# Theremizer.net
KiCad netlist of a schematic drawn in EAGLE
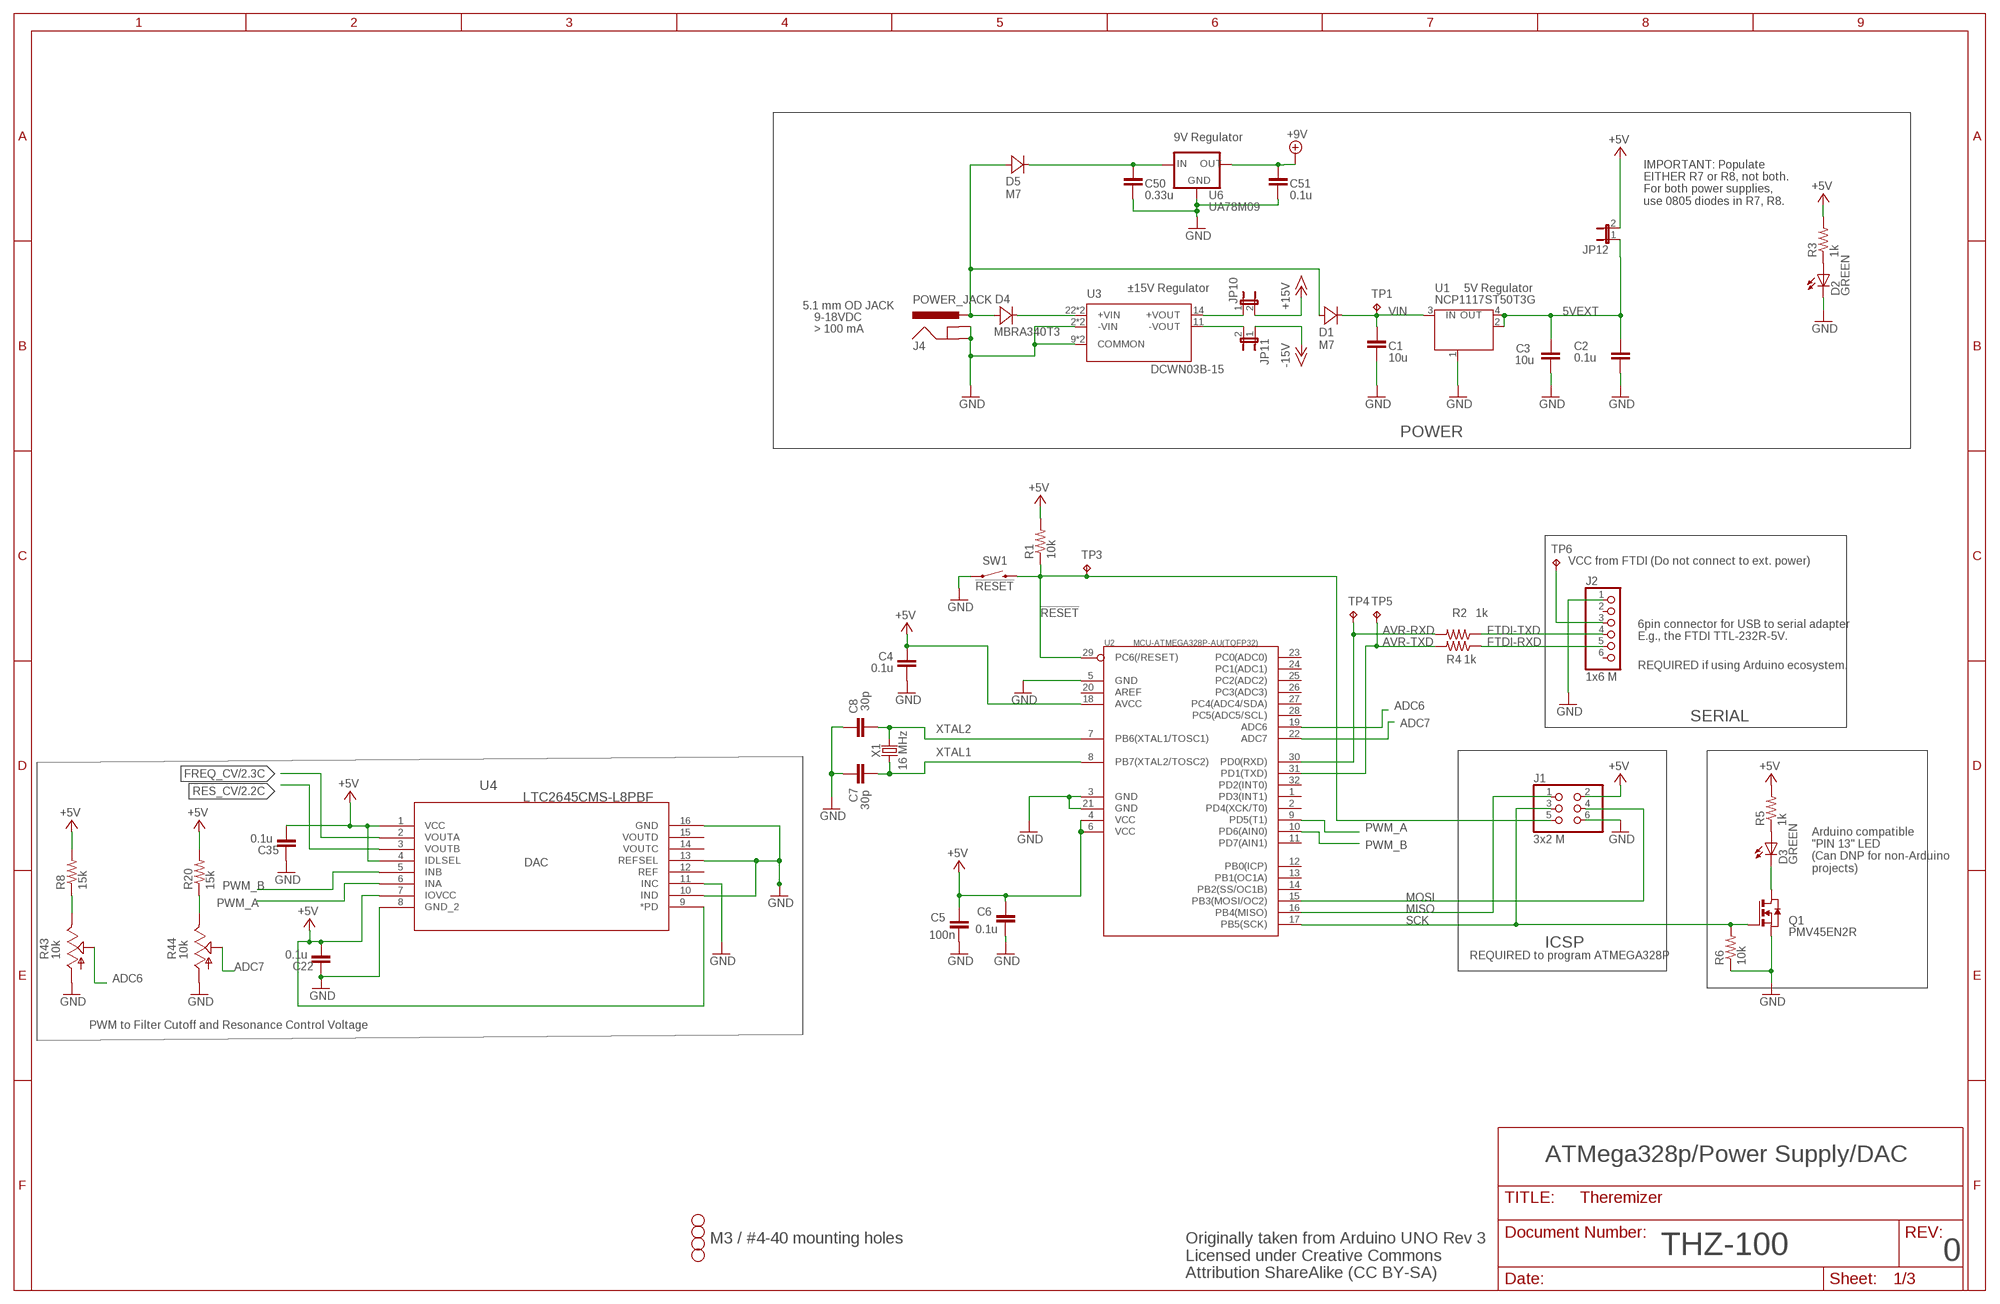
[diagram p0: schematic, sheet 1]
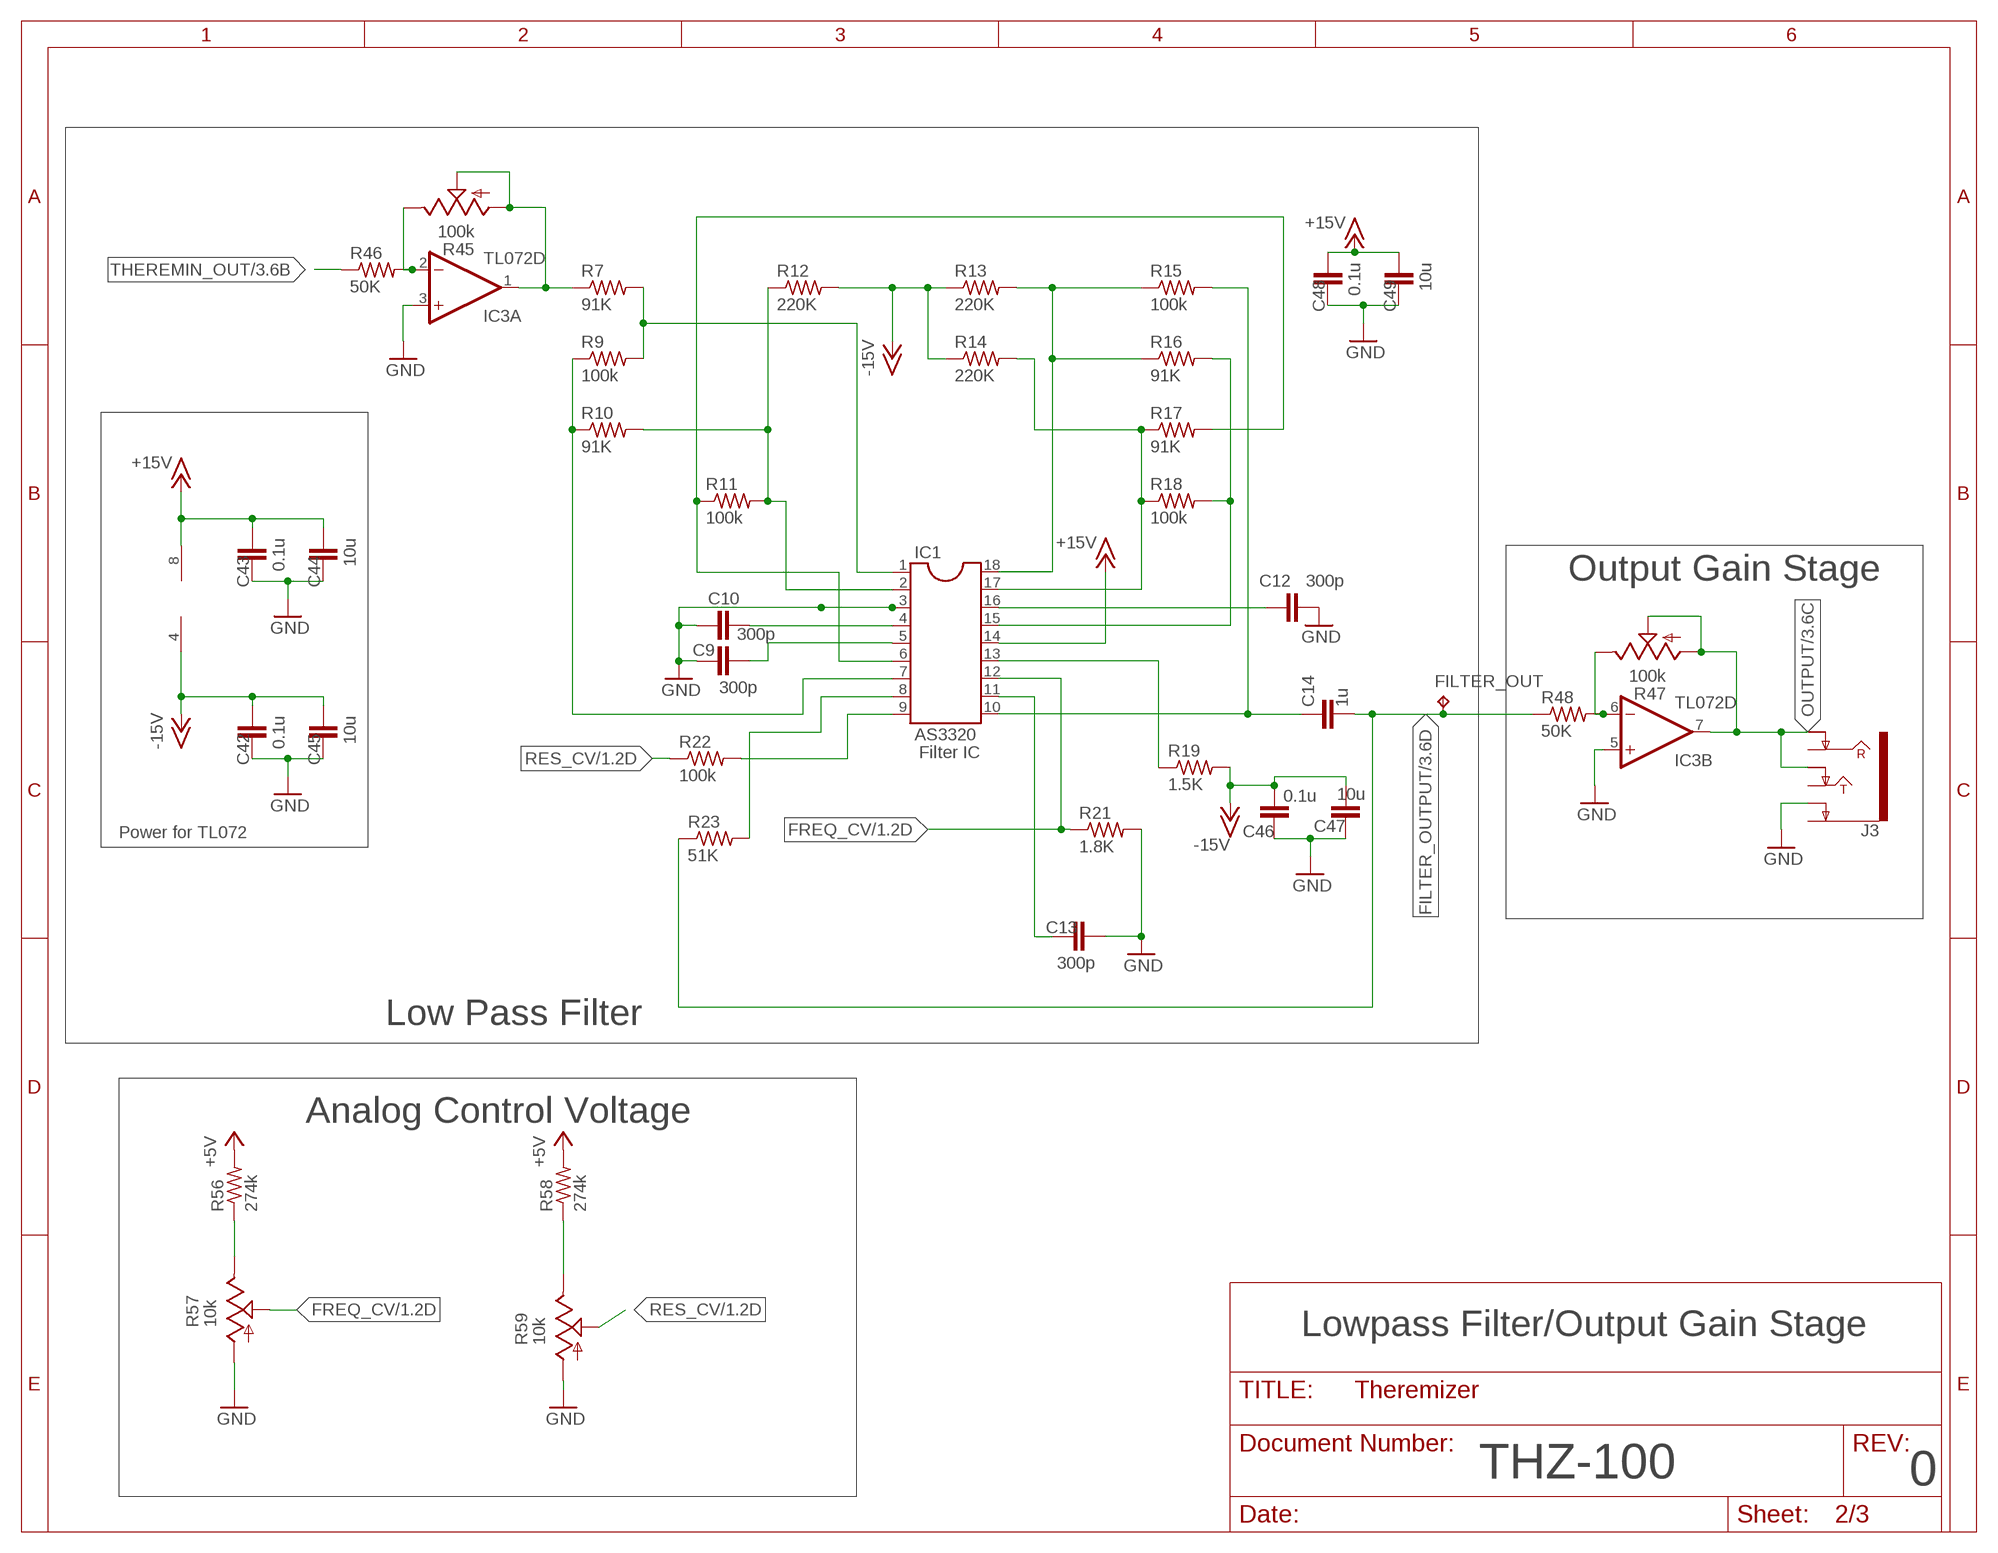
[diagram p1: schematic, sheet 2]
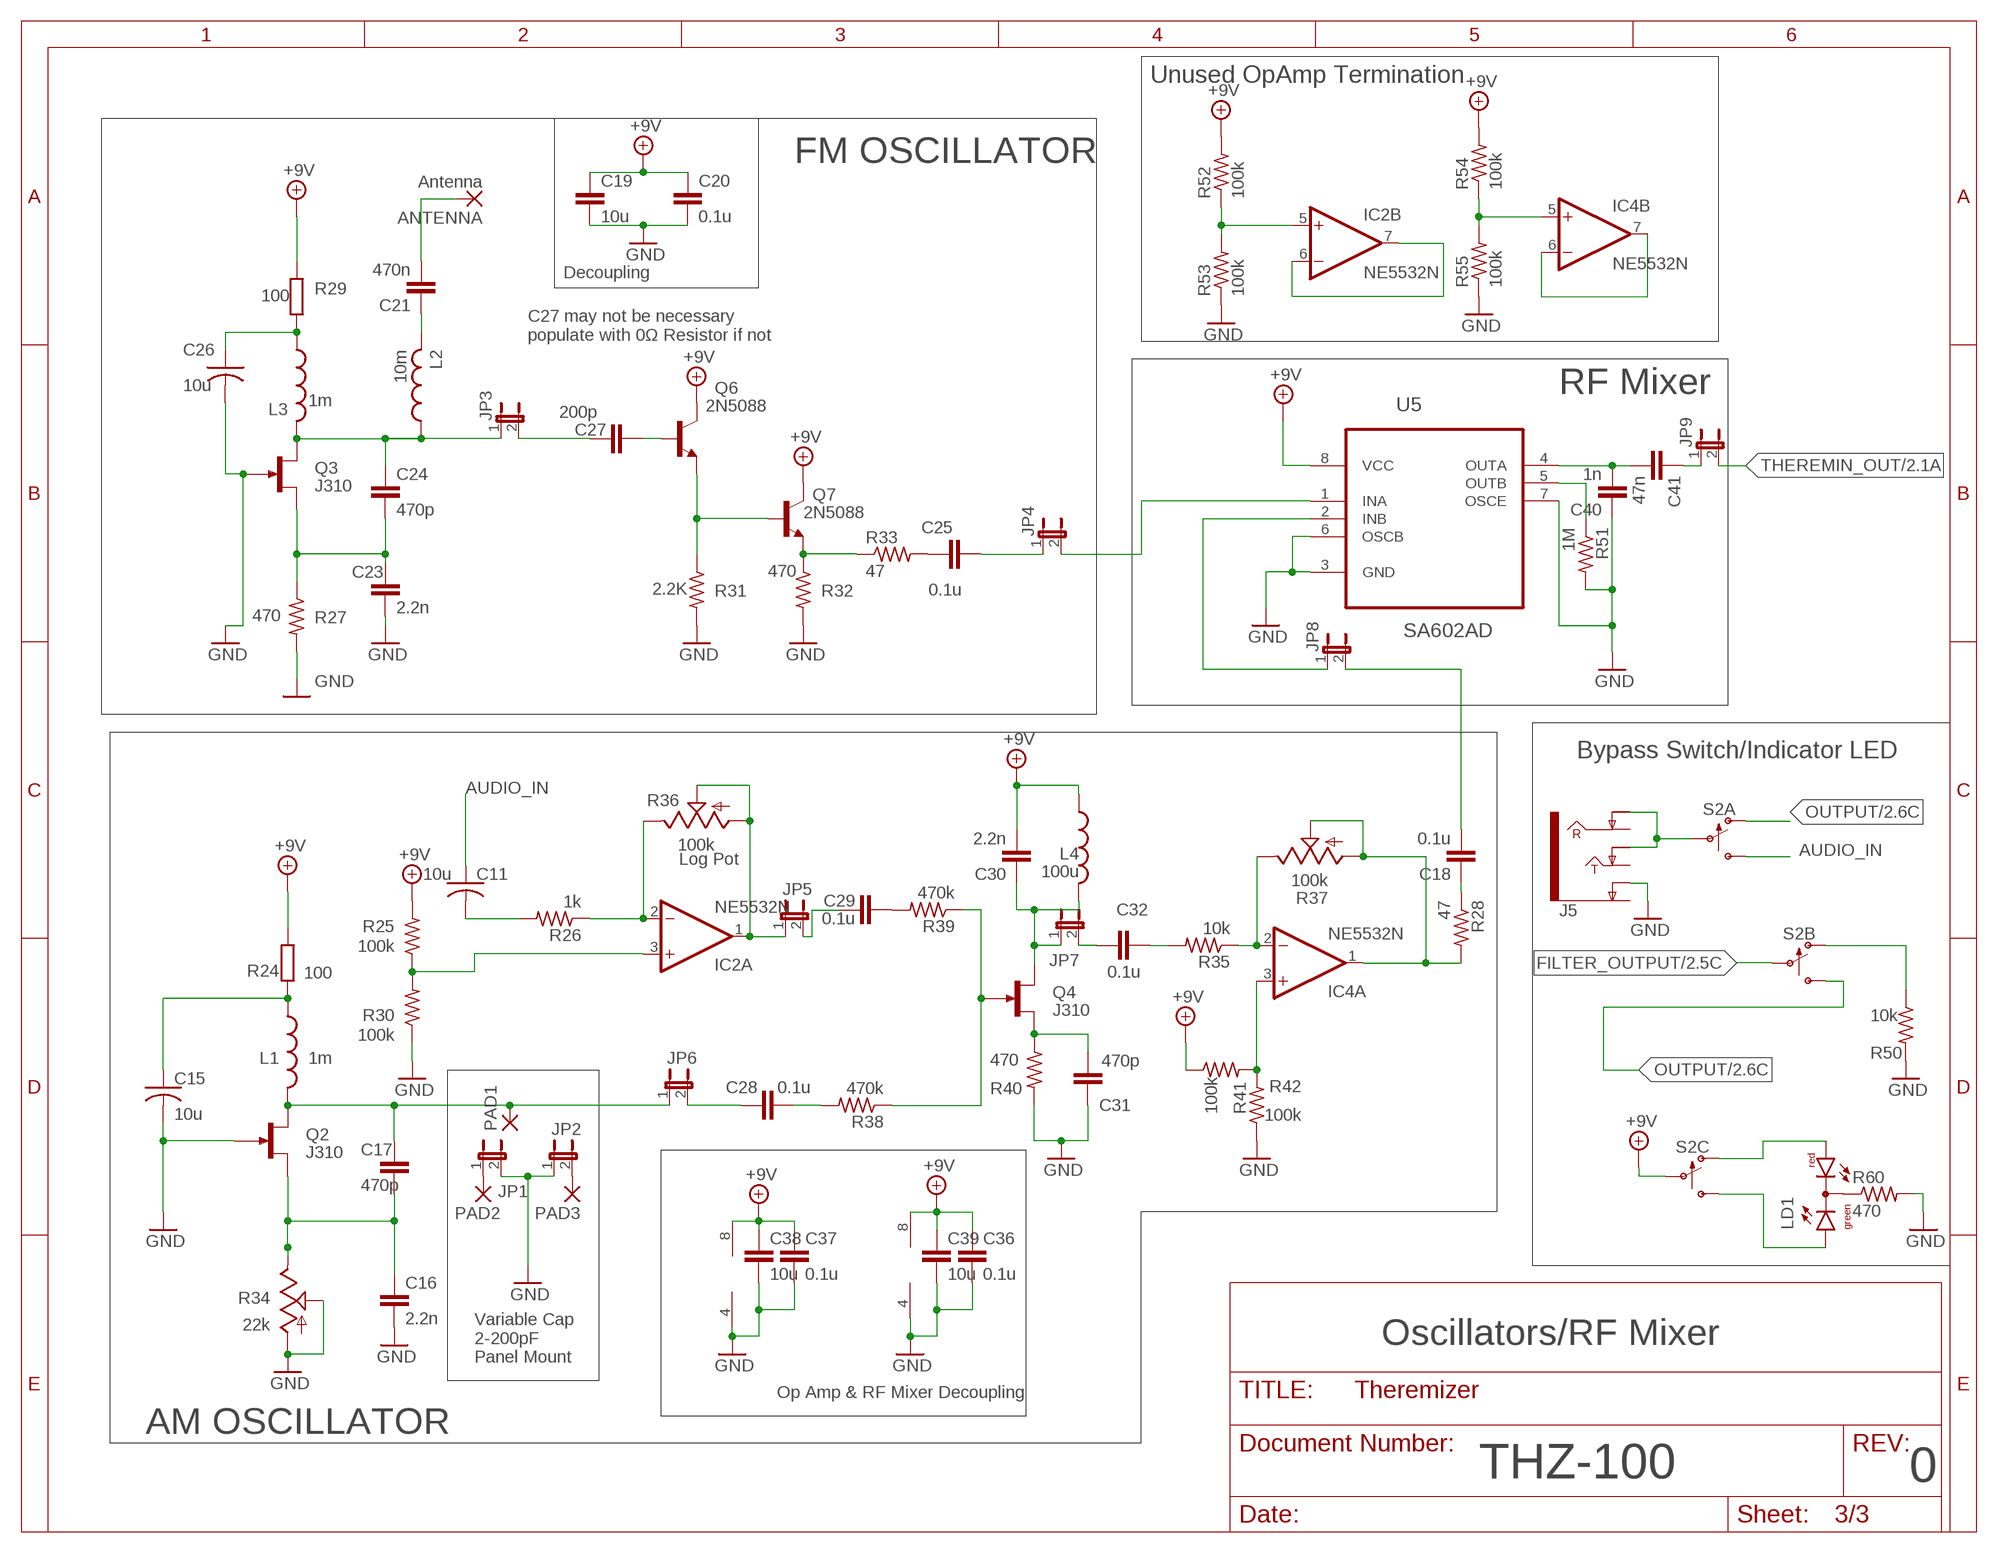
[diagram p2: schematic, sheet 3]

(export (version "E")
  (design (tool "Eeschema 10.0.6"))
  (components
    (comp (ref "ANTENNA")
      (value "Antenna")
      (footprint "eagle-import:2,54_1,1")
      (libsource (lib "eagle-import") (part "2,54/1,1"))
    )
    (comp (ref "C11")
      (value "10u")
      (footprint "eagle-import:C050-025X075")
      (libsource (lib "eagle-import") (part "C-US050-025X075"))
    )
    (comp (ref "C15")
      (value "10u")
      (footprint "eagle-import:C050-025X075")
      (libsource (lib "eagle-import") (part "C-US050-025X075"))
    )
    (comp (ref "C16")
      (value "2.2n")
      (footprint "eagle-import:C0805")
      (libsource (lib "eagle-import") (part "C-EUC0805"))
    )
    (comp (ref "C17")
      (value "470p")
      (footprint "eagle-import:C0805")
      (libsource (lib "eagle-import") (part "C-EUC0805"))
    )
    (comp (ref "C18")
      (value "0.1u")
      (footprint "eagle-import:C0805")
      (libsource (lib "eagle-import") (part "C-EUC0805"))
    )
    (comp (ref "C19")
      (value "10u")
      (footprint "eagle-import:C0805")
      (libsource (lib "eagle-import") (part "C-EUC0805"))
    )
    (comp (ref "C20")
      (value "0.1u")
      (footprint "eagle-import:C0805")
      (libsource (lib "eagle-import") (part "C-EUC0805"))
    )
    (comp (ref "C21")
      (value "470n")
      (footprint "eagle-import:C0805")
      (libsource (lib "eagle-import") (part "C-EUC0805"))
    )
    (comp (ref "C23")
      (value "2.2n")
      (footprint "eagle-import:C0805")
      (libsource (lib "eagle-import") (part "C-EUC0805"))
    )
    (comp (ref "C24")
      (value "470p")
      (footprint "eagle-import:C0805")
      (libsource (lib "eagle-import") (part "C-EUC0805"))
    )
    (comp (ref "C25")
      (value "0.1u")
      (footprint "eagle-import:C0805")
      (libsource (lib "eagle-import") (part "C-EUC0805"))
    )
    (comp (ref "C26")
      (value "10u")
      (footprint "eagle-import:C050-025X075")
      (libsource (lib "eagle-import") (part "C-US050-025X075"))
    )
    (comp (ref "C27")
      (value "200p")
      (footprint "eagle-import:C0805")
      (libsource (lib "eagle-import") (part "C-EUC0805"))
    )
    (comp (ref "C28")
      (value "0.1u")
      (footprint "eagle-import:C0805")
      (libsource (lib "eagle-import") (part "C-EUC0805"))
    )
    (comp (ref "C29")
      (value "0.1u")
      (footprint "eagle-import:C0805")
      (libsource (lib "eagle-import") (part "C-EUC0805"))
    )
    (comp (ref "C30")
      (value "2.2n")
      (footprint "eagle-import:C0805")
      (libsource (lib "eagle-import") (part "C-EUC0805"))
    )
    (comp (ref "C31")
      (value "470p")
      (footprint "eagle-import:C0805")
      (libsource (lib "eagle-import") (part "C-EUC0805"))
    )
    (comp (ref "C32")
      (value "0.1u")
      (footprint "eagle-import:C0805")
      (libsource (lib "eagle-import") (part "C-EUC0805"))
    )
    (comp (ref "C36")
      (value "0.1u")
      (footprint "eagle-import:C0805")
      (libsource (lib "eagle-import") (part "C-EUC0805"))
    )
    (comp (ref "C37")
      (value "0.1u")
      (footprint "eagle-import:C0805")
      (libsource (lib "eagle-import") (part "C-EUC0805"))
    )
    (comp (ref "C38")
      (value "10u")
      (footprint "eagle-import:C0805")
      (libsource (lib "eagle-import") (part "C-EUC0805"))
    )
    (comp (ref "C39")
      (value "10u")
      (footprint "eagle-import:C0805")
      (libsource (lib "eagle-import") (part "C-EUC0805"))
    )
    (comp (ref "C40")
      (value "1n")
      (footprint "eagle-import:C0805")
      (libsource (lib "eagle-import") (part "C-EUC0805"))
    )
    (comp (ref "C41")
      (value "47n")
      (footprint "eagle-import:C0805")
      (libsource (lib "eagle-import") (part "C-EUC0805"))
    )
    (comp (ref "IC2")
      (value "NE5532N")
      (footprint "eagle-import:DIL08")
      (libsource (lib "eagle-import") (part "NE5532N"))
    )
    (comp (ref "IC4")
      (value "NE5532N")
      (footprint "eagle-import:DIL08")
      (libsource (lib "eagle-import") (part "NE5532N"))
    )
    (comp (ref "J5")
      (value "AUDIO_JACK_TRS_0.25\"_PTH_RA")
      (footprint "eagle-import:AUDIO_JACK_0.25__TRS_PTH_RA")
      (libsource (lib "eagle-import") (part "AUDIO_JACK_TRS_0.25{dblquote}_PTH_RA"))
    )
    (comp (ref "JP1")
      (value "JP1E")
      (footprint "eagle-import:JP1")
      (libsource (lib "eagle-import") (part "JP1E"))
    )
    (comp (ref "JP2")
      (value "JP1E")
      (footprint "eagle-import:JP1")
      (libsource (lib "eagle-import") (part "JP1E"))
    )
    (comp (ref "JP3")
      (value "JP1E")
      (footprint "eagle-import:JP1")
      (libsource (lib "eagle-import") (part "JP1E"))
    )
    (comp (ref "JP4")
      (value "JP1E")
      (footprint "eagle-import:JP1")
      (libsource (lib "eagle-import") (part "JP1E"))
    )
    (comp (ref "JP5")
      (value "JP1E")
      (footprint "eagle-import:JP1")
      (libsource (lib "eagle-import") (part "JP1E"))
    )
    (comp (ref "JP6")
      (value "JP1E")
      (footprint "eagle-import:JP1")
      (libsource (lib "eagle-import") (part "JP1E"))
    )
    (comp (ref "JP7")
      (value "JP1E")
      (footprint "eagle-import:JP1")
      (libsource (lib "eagle-import") (part "JP1E"))
    )
    (comp (ref "JP8")
      (value "JP1E")
      (footprint "eagle-import:JP1")
      (libsource (lib "eagle-import") (part "JP1E"))
    )
    (comp (ref "JP9")
      (value "JP1E")
      (footprint "eagle-import:JP1")
      (libsource (lib "eagle-import") (part "JP1E"))
    )
    (comp (ref "L1")
      (value "1m")
      (footprint "eagle-import:6000-XXXX-RC")
      (libsource (lib "eagle-import") (part "L-US6000-XXX-RC"))
    )
    (comp (ref "L2")
      (value "10m")
      (footprint "eagle-import:6000-XXXX-RC")
      (libsource (lib "eagle-import") (part "L-US6000-XXX-RC"))
    )
    (comp (ref "L3")
      (value "1m")
      (footprint "eagle-import:6000-XXXX-RC")
      (libsource (lib "eagle-import") (part "L-US6000-XXX-RC"))
    )
    (comp (ref "L4")
      (value "100u")
      (footprint "eagle-import:6000-XXXX-RC")
      (libsource (lib "eagle-import") (part "L-US6000-XXX-RC"))
    )
    (comp (ref "LD1")
      (value "DUOLED-RG-C")
      (footprint "eagle-import:DUOLED-C-5MM")
      (libsource (lib "eagle-import") (part "DUOLED-RG-C"))
    )
    (comp (ref "PAD1")
      (value "2,15/1,0")
      (footprint "eagle-import:2,15_1,0")
      (libsource (lib "eagle-import") (part "2,15/1,0"))
    )
    (comp (ref "PAD2")
      (value "2,15/1,0")
      (footprint "eagle-import:2,15_1,0")
      (libsource (lib "eagle-import") (part "2,15/1,0"))
    )
    (comp (ref "PAD3")
      (value "2,15/1,0")
      (footprint "eagle-import:2,15_1,0")
      (libsource (lib "eagle-import") (part "2,15/1,0"))
    )
    (comp (ref "Q2")
      (value "J310")
      (footprint "eagle-import:TO92R")
      (libsource (lib "eagle-import") (part "J310"))
    )
    (comp (ref "Q3")
      (value "J310")
      (footprint "eagle-import:TO92R")
      (libsource (lib "eagle-import") (part "J310"))
    )
    (comp (ref "Q4")
      (value "J310")
      (footprint "eagle-import:TO92R")
      (libsource (lib "eagle-import") (part "J310"))
    )
    (comp (ref "Q6")
      (value "2N5088")
      (footprint "eagle-import:TO92")
      (libsource (lib "eagle-import") (part "2N5088"))
    )
    (comp (ref "Q7")
      (value "2N5088")
      (footprint "eagle-import:TO92")
      (libsource (lib "eagle-import") (part "2N5088"))
    )
    (comp (ref "R24")
      (value "100")
      (footprint "eagle-import:PRL1632")
      (libsource (lib "eagle-import") (part "R-EU_PRL1632"))
    )
    (comp (ref "R25")
      (value "100k")
      (footprint "eagle-import:R0805")
      (libsource (lib "eagle-import") (part "R-US_R0805"))
    )
    (comp (ref "R26")
      (value "1k")
      (footprint "eagle-import:R0805")
      (libsource (lib "eagle-import") (part "R-US_R0805"))
    )
    (comp (ref "R27")
      (value "470")
      (footprint "eagle-import:R0805")
      (libsource (lib "eagle-import") (part "R-US_R0805"))
    )
    (comp (ref "R28")
      (value "47")
      (footprint "eagle-import:R0805")
      (libsource (lib "eagle-import") (part "R-US_R0805"))
    )
    (comp (ref "R29")
      (value "100")
      (footprint "eagle-import:PRL1632")
      (libsource (lib "eagle-import") (part "R-EU_PRL1632"))
    )
    (comp (ref "R30")
      (value "100k")
      (footprint "eagle-import:R0805")
      (libsource (lib "eagle-import") (part "R-US_R0805"))
    )
    (comp (ref "R31")
      (value "2.2K")
      (footprint "eagle-import:R0805")
      (libsource (lib "eagle-import") (part "R-US_R0805"))
    )
    (comp (ref "R32")
      (value "470")
      (footprint "eagle-import:R0805")
      (libsource (lib "eagle-import") (part "R-US_R0805"))
    )
    (comp (ref "R33")
      (value "47")
      (footprint "eagle-import:R0805")
      (libsource (lib "eagle-import") (part "R-US_R0805"))
    )
    (comp (ref "R34")
      (value "22k")
      (footprint "eagle-import:B64Y")
      (libsource (lib "eagle-import") (part "TRIM_US-B64Y"))
    )
    (comp (ref "R35")
      (value "10k")
      (footprint "eagle-import:R0805")
      (libsource (lib "eagle-import") (part "R-US_R0805"))
    )
    (comp (ref "R36")
      (value "100k")
      (footprint "eagle-import:B64Y")
      (libsource (lib "eagle-import") (part "TRIM_US-B64Y"))
    )
    (comp (ref "R37")
      (value "100k")
      (footprint "eagle-import:B64Y")
      (libsource (lib "eagle-import") (part "TRIM_US-B64Y"))
    )
    (comp (ref "R38")
      (value "470k")
      (footprint "eagle-import:R0805")
      (libsource (lib "eagle-import") (part "R-US_R0805"))
    )
    (comp (ref "R39")
      (value "470k")
      (footprint "eagle-import:R0805")
      (libsource (lib "eagle-import") (part "R-US_R0805"))
    )
    (comp (ref "R40")
      (value "470")
      (footprint "eagle-import:R0805")
      (libsource (lib "eagle-import") (part "R-US_R0805"))
    )
    (comp (ref "R41")
      (value "100k")
      (footprint "eagle-import:R0805")
      (libsource (lib "eagle-import") (part "R-US_R0805"))
    )
    (comp (ref "R42")
      (value "100k")
      (footprint "eagle-import:R0805")
      (libsource (lib "eagle-import") (part "R-US_R0805"))
    )
    (comp (ref "R50")
      (value "10k")
      (footprint "eagle-import:R0805")
      (libsource (lib "eagle-import") (part "R-US_R0805"))
    )
    (comp (ref "R51")
      (value "1M")
      (footprint "eagle-import:R0805")
      (libsource (lib "eagle-import") (part "R-US_R0805"))
    )
    (comp (ref "R52")
      (value "100k")
      (footprint "eagle-import:R0805")
      (libsource (lib "eagle-import") (part "R-US_R0805"))
    )
    (comp (ref "R53")
      (value "100k")
      (footprint "eagle-import:R0805")
      (libsource (lib "eagle-import") (part "R-US_R0805"))
    )
    (comp (ref "R54")
      (value "100k")
      (footprint "eagle-import:R0805")
      (libsource (lib "eagle-import") (part "R-US_R0805"))
    )
    (comp (ref "R55")
      (value "100k")
      (footprint "eagle-import:R0805")
      (libsource (lib "eagle-import") (part "R-US_R0805"))
    )
    (comp (ref "R60")
      (value "470")
      (footprint "eagle-import:R0805")
      (libsource (lib "eagle-import") (part "R-US_R0805"))
    )
    (comp (ref "S2")
      (value "SWITCH-3PDT-PTH-STOMP")
      (footprint "eagle-import:STOMP_SWITCH_3PDT")
      (libsource (lib "eagle-import") (part "SWITCH-3PDT-PTH-STOMP"))
    )
    (comp (ref "U5")
      (value "SA602AD")
      (footprint "eagle-import:SO8")
      (libsource (lib "eagle-import") (part "SA602AD"))
    )
    (comp (ref "C1")
      (value "10u")
      (footprint "eagle-import:C0805")
      (fields (field (name "MFR") "Samsung") (field (name "MPN") "CL21A106KOQNNNG"))
      (libsource (lib "eagle-import") (part "C-EUC0805"))
    )
    (comp (ref "C2")
      (value "0.1u")
      (footprint "eagle-import:C0805")
      (fields (field (name "MFR") "Samsung") (field (name "MPN") "CL21B104KBCNNNC"))
      (libsource (lib "eagle-import") (part "C-EUC0805"))
    )
    (comp (ref "C3")
      (value "10u")
      (footprint "eagle-import:C0805")
      (fields (field (name "MFR") "Samsung") (field (name "MPN") "CL21A106KOQNNNG"))
      (libsource (lib "eagle-import") (part "C-EUC0805"))
    )
    (comp (ref "C4")
      (value "0.1u")
      (footprint "eagle-import:C0805")
      (fields (field (name "MFR") "Samsung") (field (name "MPN") "CL21B104KBCNNNC"))
      (libsource (lib "eagle-import") (part "C-EUC0805"))
    )
    (comp (ref "C5")
      (value "100n")
      (footprint "eagle-import:C0805")
      (fields (field (name "MFR") "Samsung") (field (name "MPN") "CL21B104KBCNNNC"))
      (libsource (lib "eagle-import") (part "C-EUC0805"))
    )
    (comp (ref "C6")
      (value "0.1u")
      (footprint "eagle-import:C0805")
      (fields (field (name "MFR") "Samsung") (field (name "MPN") "CL21B104KBCNNNC"))
      (libsource (lib "eagle-import") (part "C-EUC0805"))
    )
    (comp (ref "C7")
      (value "30p")
      (footprint "eagle-import:C0805")
      (fields (field (name "MFR") "Samsung") (field (name "MPN") "CL21C180JBANNNC"))
      (libsource (lib "eagle-import") (part "C-EUC0805"))
    )
    (comp (ref "C8")
      (value "30p")
      (footprint "eagle-import:C0805")
      (fields (field (name "MFR") "Samsung") (field (name "MPN") "CL21C300JBANNNC"))
      (libsource (lib "eagle-import") (part "C-EUC0805"))
    )
    (comp (ref "C22")
      (value "0.1u")
      (footprint "eagle-import:C0805K")
      (fields (field (name "MFR") "Samsung") (field (name "MPN") "CL21C300JBANNNC"))
      (libsource (lib "eagle-import") (part "C-EUC0805K"))
    )
    (comp (ref "C35")
      (value "0.1u")
      (footprint "eagle-import:C0805")
      (fields (field (name "MFR") "Samsung") (field (name "MPN") "CL21C300JBANNNC"))
      (libsource (lib "eagle-import") (part "C-EUC0805"))
    )
    (comp (ref "C50")
      (value "0.33u")
      (footprint "eagle-import:C0805")
      (fields (field (name "MFR") "Samsung") (field (name "MPN") "CL21A106KOQNNNG"))
      (libsource (lib "eagle-import") (part "C-EUC0805"))
    )
    (comp (ref "C51")
      (value "0.1u")
      (footprint "eagle-import:C0805")
      (fields (field (name "MFR") "Samsung") (field (name "MPN") "CL21A106KOQNNNG"))
      (libsource (lib "eagle-import") (part "C-EUC0805"))
    )
    (comp (ref "D1")
      (value "M7")
      (footprint "eagle-import:SMA")
      (fields (field (name "MFR") "SMC Diode") (field (name "MPN") "10BQ030TR"))
      (libsource (lib "eagle-import") (part "MBRA340T3"))
    )
    (comp (ref "D2")
      (value "GREEN")
      (footprint "eagle-import:CHIP-LED0805")
      (fields (field (name "MFR") "Würth Elektronik") (field (name "MPN") "150080GS75000"))
      (libsource (lib "eagle-import") (part "LEDCHIP-LED0805"))
    )
    (comp (ref "D3")
      (value "GREEN")
      (footprint "eagle-import:CHIP-LED0805")
      (fields (field (name "MFR") "Würth Elektronik") (field (name "MPN") "150080GS75000"))
      (libsource (lib "eagle-import") (part "LEDCHIP-LED0805"))
    )
    (comp (ref "D4")
      (value "MBRA340T3")
      (footprint "eagle-import:SMA")
      (libsource (lib "eagle-import") (part "MBRA340T3"))
    )
    (comp (ref "D5")
      (value "M7")
      (footprint "eagle-import:SMA")
      (fields (field (name "MFR") "SMC Diode") (field (name "MPN") "10BQ030TR"))
      (libsource (lib "eagle-import") (part "MBRA340T3"))
    )
    (comp (ref "H1")
      (value "STAND-OFF")
      (footprint "eagle-import:STAND-OFF")
      (libsource (lib "eagle-import") (part "STAND-OFF"))
    )
    (comp (ref "H2")
      (value "STAND-OFF")
      (footprint "eagle-import:STAND-OFF")
      (libsource (lib "eagle-import") (part "STAND-OFF"))
    )
    (comp (ref "H3")
      (value "STAND-OFF")
      (footprint "eagle-import:STAND-OFF")
      (libsource (lib "eagle-import") (part "STAND-OFF"))
    )
    (comp (ref "H4")
      (value "STAND-OFF")
      (footprint "eagle-import:STAND-OFF")
      (libsource (lib "eagle-import") (part "STAND-OFF"))
    )
    (comp (ref "J1")
      (value "3x2 M")
      (footprint "eagle-import:2X03")
      (fields (field (name "MFR") "Harwin") (field (name "MPN") "M20-9980345"))
      (libsource (lib "eagle-import") (part "PINHD-2X3"))
    )
    (comp (ref "J2")
      (value "1x6 M")
      (footprint "eagle-import:1X06")
      (fields (field (name "MFR") "Sullins") (field (name "MPN") "PRPC006SAAN-RC"))
      (libsource (lib "eagle-import") (part "PINHD-1X6"))
    )
    (comp (ref "J4")
      (value "POWER_JACK")
      (footprint "eagle-import:POWER_JACK_PTH")
      (fields (field (name "MFR") "CUI") (field (name "MPN") "PJ-202A"))
      (libsource (lib "eagle-import") (part "POWER_JACK"))
    )
    (comp (ref "JP10")
      (value "JP1E")
      (footprint "eagle-import:JP1")
      (libsource (lib "eagle-import") (part "JP1E"))
    )
    (comp (ref "JP11")
      (value "JP1E")
      (footprint "eagle-import:JP1")
      (libsource (lib "eagle-import") (part "JP1E"))
    )
    (comp (ref "JP12")
      (value "JP1E")
      (footprint "eagle-import:JP1")
      (libsource (lib "eagle-import") (part "JP1E"))
    )
    (comp (ref "Q1")
      (value "PMV45EN2R")
      (footprint "eagle-import:SOT-23")
      (fields (field (name "MFR") "Nexperia") (field (name "MPN") "PMV45EN2R"))
      (libsource (lib "eagle-import") (part "NMOSSOT23"))
    )
    (comp (ref "R1")
      (value "10k")
      (footprint "eagle-import:R0805")
      (fields (field (name "MFR") "Yageo") (field (name "MPN") "RC0805FR-0710KL"))
      (libsource (lib "eagle-import") (part "R-US_R0805"))
    )
    (comp (ref "R2")
      (value "1k")
      (footprint "eagle-import:R0805")
      (fields (field (name "MFR") "Yageo") (field (name "MPN") "RC0805FR-071KL"))
      (libsource (lib "eagle-import") (part "R-US_R0805"))
    )
    (comp (ref "R3")
      (value "1k")
      (footprint "eagle-import:R0805")
      (fields (field (name "MFR") "Yageo") (field (name "MPN") "RC0805FR-071KL"))
      (libsource (lib "eagle-import") (part "R-US_R0805"))
    )
    (comp (ref "R4")
      (value "1k")
      (footprint "eagle-import:R0805")
      (fields (field (name "MFR") "Yageo") (field (name "MPN") "RC0805FR-071KL"))
      (libsource (lib "eagle-import") (part "R-US_R0805"))
    )
    (comp (ref "R5")
      (value "1k")
      (footprint "eagle-import:R0805")
      (fields (field (name "MFR") "Yageo") (field (name "MPN") "RC0805FR-071KL"))
      (libsource (lib "eagle-import") (part "R-US_R0805"))
    )
    (comp (ref "R6")
      (value "10k")
      (footprint "eagle-import:R0805")
      (fields (field (name "MFR") "Yageo") (field (name "MPN") "RC0805FR-0710KL"))
      (libsource (lib "eagle-import") (part "R-US_R0805"))
    )
    (comp (ref "R8")
      (value "15k")
      (footprint "eagle-import:R0805")
      (fields (field (name "MFR") "Yageo") (field (name "MPN") "RC0805FR-0710KL"))
      (libsource (lib "eagle-import") (part "R-US_R0805"))
    )
    (comp (ref "R20")
      (value "15k")
      (footprint "eagle-import:R0805")
      (fields (field (name "MFR") "Yageo") (field (name "MPN") "RC0805FR-0710KL"))
      (libsource (lib "eagle-import") (part "R-US_R0805"))
    )
    (comp (ref "R43")
      (value "10k")
      (footprint "eagle-import:B64Y")
      (libsource (lib "eagle-import") (part "TRIM_US-B64Y"))
    )
    (comp (ref "R44")
      (value "10k")
      (footprint "eagle-import:B64Y")
      (libsource (lib "eagle-import") (part "TRIM_US-B64Y"))
    )
    (comp (ref "SW1")
      (value "!RESET")
      (footprint "eagle-import:TACTILE_SWITCH_SMD")
      (fields (field (name "MFR") "C&K") (field (name "MPN") "RS-187R05A2-DS MT RT"))
      (libsource (lib "eagle-import") (part "SWITCH-MOMENTARY-2SMD"))
    )
    (comp (ref "TP1")
      (value "TPPAD1-13")
      (footprint "eagle-import:P1-13")
      (libsource (lib "eagle-import") (part "TPPAD1-13"))
    )
    (comp (ref "TP3")
      (value "TPPAD1-13")
      (footprint "eagle-import:P1-13")
      (libsource (lib "eagle-import") (part "TPPAD1-13"))
    )
    (comp (ref "TP4")
      (value "TPPAD1-13")
      (footprint "eagle-import:P1-13")
      (libsource (lib "eagle-import") (part "TPPAD1-13"))
    )
    (comp (ref "TP5")
      (value "TPPAD1-13")
      (footprint "eagle-import:P1-13")
      (libsource (lib "eagle-import") (part "TPPAD1-13"))
    )
    (comp (ref "TP6")
      (value "TPPAD1-13")
      (footprint "eagle-import:P1-13")
      (libsource (lib "eagle-import") (part "TPPAD1-13"))
    )
    (comp (ref "U1")
      (value "NCP1117ST50T3G")
      (footprint "eagle-import:SOT223")
      (fields (field (name "MFR") "ON Semiconductor"))
      (libsource (lib "eagle-import") (part "MC33269ST-3.3T3"))
    )
    (comp (ref "U2")
      (value "MCU-ATMEGA328P-AU(TQFP32)")
      (footprint "eagle-import:TQFP32-0.8-7X7MM")
      (fields
        (field (name "DIGI-KEY_PART_NUMBER") "ATMEGA328P-AU-ND")
        (field (name "MF") "Microchip")
        (field (name "MP") "ATMEGA328P-AU")
      )
      (libsource (lib "eagle-import") (part "MCU-ATMEGA328P-AU(TQFP32)"))
    )
    (comp (ref "U3")
      (value "DCWN03B-15")
      (footprint "eagle-import:DIP1549W45P254L3404H940Q24")
      (libsource (lib "eagle-import") (part "DCWN03"))
    )
    (comp (ref "U4")
      (value "LTC2645CMS-L8PBF")
      (footprint "eagle-import:MSOP-16_MS")
      (fields (field (name "MF") "Linear Technology/Analog") (field (name "MP") "LTC2645CMS-L8#PBF"))
      (libsource (lib "eagle-import") (part "LTC2645CMS-L8PBF"))
    )
    (comp (ref "U6")
      (value "UA78M09")
      (footprint "eagle-import:DPACK")
      (libsource (lib "eagle-import") (part "µA78MX"))
    )
    (comp (ref "X1")
      (value "16 MHz")
      (footprint "eagle-import:HC49UP")
      (fields (field (name "MFR") "ECS") (field (name "MPN") "ECS-160-18-5PX-TR"))
      (libsource (lib "eagle-import") (part "CRYSTALSMD-HC49UP"))
    )
    (comp (ref "C9")
      (value "300p")
      (footprint "eagle-import:C0805")
      (libsource (lib "eagle-import") (part "C-EUC0805"))
    )
    (comp (ref "C10")
      (value "300p")
      (footprint "eagle-import:C0805")
      (libsource (lib "eagle-import") (part "C-EUC0805"))
    )
    (comp (ref "C12")
      (value "300p")
      (footprint "eagle-import:C0805")
      (libsource (lib "eagle-import") (part "C-EUC0805"))
    )
    (comp (ref "C13")
      (value "300p")
      (footprint "eagle-import:C0805")
      (libsource (lib "eagle-import") (part "C-EUC0805"))
    )
    (comp (ref "C14")
      (value "1u")
      (footprint "eagle-import:C0805")
      (libsource (lib "eagle-import") (part "C-EUC0805"))
    )
    (comp (ref "C42")
      (value "0.1u")
      (footprint "eagle-import:C0805")
      (libsource (lib "eagle-import") (part "C-EUC0805"))
    )
    (comp (ref "C43")
      (value "0.1u")
      (footprint "eagle-import:C0805")
      (libsource (lib "eagle-import") (part "C-EUC0805"))
    )
    (comp (ref "C44")
      (value "10u")
      (footprint "eagle-import:C0805")
      (libsource (lib "eagle-import") (part "C-EUC0805"))
    )
    (comp (ref "C45")
      (value "10u")
      (footprint "eagle-import:C0805")
      (libsource (lib "eagle-import") (part "C-EUC0805"))
    )
    (comp (ref "C46")
      (value "0.1u")
      (footprint "eagle-import:C0805")
      (libsource (lib "eagle-import") (part "C-EUC0805"))
    )
    (comp (ref "C47")
      (value "10u")
      (footprint "eagle-import:C0805")
      (libsource (lib "eagle-import") (part "C-EUC0805"))
    )
    (comp (ref "C48")
      (value "0.1u")
      (footprint "eagle-import:C0805")
      (libsource (lib "eagle-import") (part "C-EUC0805"))
    )
    (comp (ref "C49")
      (value "10u")
      (footprint "eagle-import:C0805")
      (libsource (lib "eagle-import") (part "C-EUC0805"))
    )
    (comp (ref "FILTER_OUT")
      (value "TPB2,54")
      (footprint "eagle-import:B2,54")
      (libsource (lib "eagle-import") (part "TPB2,54"))
    )
    (comp (ref "IC1")
      (value "AS3320")
      (footprint "eagle-import:SOCKET-18")
      (libsource (lib "eagle-import") (part "DIL18S"))
    )
    (comp (ref "IC3")
      (value "TL072D")
      (footprint "eagle-import:SO08")
      (libsource (lib "eagle-import") (part "TL072D"))
    )
    (comp (ref "J3")
      (value "AUDIO_JACK_TRS_0.25\"_PTH_RA")
      (footprint "eagle-import:AUDIO_JACK_0.25__TRS_PTH_RA")
      (libsource (lib "eagle-import") (part "AUDIO_JACK_TRS_0.25{dblquote}_PTH_RA"))
    )
    (comp (ref "R7")
      (value "91K")
      (footprint "eagle-import:R0805")
      (libsource (lib "eagle-import") (part "R-US_R0805"))
    )
    (comp (ref "R9")
      (value "100k")
      (footprint "eagle-import:R0805")
      (libsource (lib "eagle-import") (part "R-US_R0805"))
    )
    (comp (ref "R10")
      (value "91K")
      (footprint "eagle-import:R0805")
      (libsource (lib "eagle-import") (part "R-US_R0805"))
    )
    (comp (ref "R11")
      (value "100k")
      (footprint "eagle-import:R0805")
      (libsource (lib "eagle-import") (part "R-US_R0805"))
    )
    (comp (ref "R12")
      (value "220K")
      (footprint "eagle-import:R0805")
      (libsource (lib "eagle-import") (part "R-US_R0805"))
    )
    (comp (ref "R13")
      (value "220K")
      (footprint "eagle-import:R0805")
      (libsource (lib "eagle-import") (part "R-US_R0805"))
    )
    (comp (ref "R14")
      (value "220K")
      (footprint "eagle-import:R0805")
      (libsource (lib "eagle-import") (part "R-US_R0805"))
    )
    (comp (ref "R15")
      (value "100k")
      (footprint "eagle-import:R0805")
      (libsource (lib "eagle-import") (part "R-US_R0805"))
    )
    (comp (ref "R16")
      (value "91K")
      (footprint "eagle-import:R0805")
      (libsource (lib "eagle-import") (part "R-US_R0805"))
    )
    (comp (ref "R17")
      (value "91K")
      (footprint "eagle-import:R0805")
      (libsource (lib "eagle-import") (part "R-US_R0805"))
    )
    (comp (ref "R18")
      (value "100k")
      (footprint "eagle-import:R0805")
      (libsource (lib "eagle-import") (part "R-US_R0805"))
    )
    (comp (ref "R19")
      (value "1.5K")
      (footprint "eagle-import:R0805")
      (libsource (lib "eagle-import") (part "R-US_R0805"))
    )
    (comp (ref "R21")
      (value "1.8K")
      (footprint "eagle-import:R0805")
      (libsource (lib "eagle-import") (part "R-US_R0805"))
    )
    (comp (ref "R22")
      (value "100k")
      (footprint "eagle-import:R0805")
      (libsource (lib "eagle-import") (part "R-US_R0805"))
    )
    (comp (ref "R23")
      (value "51K")
      (footprint "eagle-import:R0805")
      (libsource (lib "eagle-import") (part "R-US_R0805"))
    )
    (comp (ref "R45")
      (value "100k")
      (footprint "eagle-import:B64Y")
      (libsource (lib "eagle-import") (part "TRIM_US-B64Y"))
    )
    (comp (ref "R46")
      (value "50K")
      (footprint "eagle-import:R0805")
      (libsource (lib "eagle-import") (part "R-US_R0805"))
    )
    (comp (ref "R47")
      (value "100k")
      (footprint "eagle-import:B64Y")
      (libsource (lib "eagle-import") (part "TRIM_US-B64Y"))
    )
    (comp (ref "R48")
      (value "50K")
      (footprint "eagle-import:R0805")
      (libsource (lib "eagle-import") (part "R-US_R0805"))
    )
    (comp (ref "R56")
      (value "274k")
      (footprint "eagle-import:R0805")
      (libsource (lib "eagle-import") (part "R-US_R0805"))
    )
    (comp (ref "R57")
      (value "10k")
      (footprint "eagle-import:B64Y")
      (libsource (lib "eagle-import") (part "TRIM_US-B64Y"))
    )
    (comp (ref "R58")
      (value "274k")
      (footprint "eagle-import:R0805")
      (libsource (lib "eagle-import") (part "R-US_R0805"))
    )
    (comp (ref "R59")
      (value "10k")
      (footprint "eagle-import:B64Y")
      (libsource (lib "eagle-import") (part "TRIM_US-B64Y"))
    )
  )
  (nets
    (net (code "1") (name "+5V") (class "Default")
      (node (ref "C22") (pin "1") (pinfunction "1_1") (pintype "passive"))
      (node (ref "C35") (pin "1") (pinfunction "1_1") (pintype "passive"))
      (node (ref "C4") (pin "2") (pinfunction "2_2") (pintype "passive"))
      (node (ref "C5") (pin "2") (pinfunction "2_2") (pintype "passive"))
      (node (ref "C6") (pin "2") (pinfunction "2_2") (pintype "passive"))
      (node (ref "J1") (pin "2") (pinfunction "2_2") (pintype "passive"))
      (node (ref "JP12") (pin "2") (pinfunction "2_2") (pintype "passive"))
      (node (ref "R1") (pin "2") (pinfunction "2_2") (pintype "passive"))
      (node (ref "R20") (pin "2") (pinfunction "2_2") (pintype "passive"))
      (node (ref "R3") (pin "2") (pinfunction "2_2") (pintype "passive"))
      (node (ref "R5") (pin "2") (pinfunction "2_2") (pintype "passive"))
      (node (ref "R56") (pin "2") (pinfunction "2_2") (pintype "passive"))
      (node (ref "R58") (pin "2") (pinfunction "2_2") (pintype "passive"))
      (node (ref "R8") (pin "2") (pinfunction "2_2") (pintype "passive"))
      (node (ref "U2") (pin "18") (pinfunction "AVCC_18") (pintype "bidirectional"))
      (node (ref "U2") (pin "4") (pinfunction "VCC_4") (pintype "bidirectional"))
      (node (ref "U2") (pin "6") (pinfunction "VCC_6") (pintype "bidirectional"))
      (node (ref "U4") (pin "1") (pinfunction "VCC_1") (pintype "power_in"))
      (node (ref "U4") (pin "4") (pinfunction "IDLSEL_4") (pintype "input"))
      (node (ref "U4") (pin "7") (pinfunction "IOVCC_7") (pintype "bidirectional"))
      (node (ref "U4") (pin "9") (pinfunction "*PD_9") (pintype "input"))
    )
    (net (code "2") (name "+9V") (class "Default")
      (node (ref "C19") (pin "1") (pinfunction "1_1") (pintype "passive"))
      (node (ref "C20") (pin "1") (pinfunction "1_1") (pintype "passive"))
      (node (ref "C30") (pin "2") (pinfunction "2_2") (pintype "passive"))
      (node (ref "C36") (pin "1") (pinfunction "1_1") (pintype "passive"))
      (node (ref "C37") (pin "1") (pinfunction "1_1") (pintype "passive"))
      (node (ref "C38") (pin "1") (pinfunction "1_1") (pintype "passive"))
      (node (ref "C39") (pin "1") (pinfunction "1_1") (pintype "passive"))
      (node (ref "C51") (pin "1") (pinfunction "1_1") (pintype "passive"))
      (node (ref "IC2") (pin "8") (pinfunction "V+_8") (pintype "power_in"))
      (node (ref "IC4") (pin "8") (pinfunction "V+_8") (pintype "power_in"))
      (node (ref "L4") (pin "1") (pinfunction "1_1") (pintype "passive"))
      (node (ref "Q6") (pin "1") (pinfunction "C_1") (pintype "passive"))
      (node (ref "Q7") (pin "1") (pinfunction "C_1") (pintype "passive"))
      (node (ref "R24") (pin "2") (pinfunction "2_2") (pintype "passive"))
      (node (ref "R25") (pin "2") (pinfunction "2_2") (pintype "passive"))
      (node (ref "R29") (pin "1") (pinfunction "1_1") (pintype "passive"))
      (node (ref "R41") (pin "1") (pinfunction "1_1") (pintype "passive"))
      (node (ref "R52") (pin "2") (pinfunction "2_2") (pintype "passive"))
      (node (ref "R54") (pin "2") (pinfunction "2_2") (pintype "passive"))
      (node (ref "S2") (pin "P$8") (pinfunction "P_P$8") (pintype "passive"))
      (node (ref "U5") (pin "8") (pinfunction "VCC_8") (pintype "power_in"))
      (node (ref "U6") (pin "3") (pinfunction "OUT_3") (pintype "passive"))
    )
    (net (code "3") (name "+15V") (class "Default")
      (node (ref "C43") (pin "2") (pinfunction "2_2") (pintype "passive"))
      (node (ref "C44") (pin "2") (pinfunction "2_2") (pintype "passive"))
      (node (ref "C48") (pin "2") (pinfunction "2_2") (pintype "passive"))
      (node (ref "C49") (pin "2") (pinfunction "2_2") (pintype "passive"))
      (node (ref "IC1") (pin "14") (pinfunction "14_14") (pintype "passive"))
      (node (ref "IC3") (pin "8") (pinfunction "V+_8") (pintype "power_in"))
      (node (ref "JP10") (pin "2") (pinfunction "2_2") (pintype "passive"))
    )
    (net (code "4") (name "-15V") (class "Default")
      (node (ref "C42") (pin "2") (pinfunction "2_2") (pintype "passive"))
      (node (ref "C45") (pin "2") (pinfunction "2_2") (pintype "passive"))
      (node (ref "C46") (pin "2") (pinfunction "2_2") (pintype "passive"))
      (node (ref "C47") (pin "2") (pinfunction "2_2") (pintype "passive"))
      (node (ref "IC3") (pin "4") (pinfunction "V-_4") (pintype "power_in"))
      (node (ref "JP11") (pin "1") (pinfunction "1_1") (pintype "passive"))
      (node (ref "R12") (pin "2") (pinfunction "2_2") (pintype "passive"))
      (node (ref "R13") (pin "1") (pinfunction "1_1") (pintype "passive"))
      (node (ref "R14") (pin "1") (pinfunction "1_1") (pintype "passive"))
      (node (ref "R19") (pin "2") (pinfunction "2_2") (pintype "passive"))
    )
    (net (code "5") (name "5VEXT") (class "Default")
      (node (ref "C2") (pin "2") (pinfunction "2_2") (pintype "passive"))
      (node (ref "C3") (pin "1") (pinfunction "1_1") (pintype "passive"))
      (node (ref "JP12") (pin "1") (pinfunction "1_1") (pintype "passive"))
      (node (ref "U1") (pin "2") (pinfunction "OUT_2") (pintype "passive"))
      (node (ref "U1") (pin "4") (pinfunction "OUT_4") (pintype "passive"))
    )
    (net (code "6") (name "ADC6") (class "Default")
      (node (ref "R43") (pin "S") (pinfunction "S_S") (pintype "passive"))
      (node (ref "U2") (pin "19") (pinfunction "ADC6_19") (pintype "bidirectional"))
    )
    (net (code "7") (name "ADC7") (class "Default")
      (node (ref "R44") (pin "S") (pinfunction "S_S") (pintype "passive"))
      (node (ref "U2") (pin "22") (pinfunction "ADC7_22") (pintype "bidirectional"))
    )
    (net (code "8") (name "AUDIO_IN") (class "Default")
      (node (ref "C11") (pin "1") (pinfunction "1_1") (pintype "passive"))
      (node (ref "S2") (pin "P$3") (pinfunction "S_P$3") (pintype "passive"))
    )
    (net (code "9") (name "AVR-RXD") (class "Default")
      (node (ref "R2") (pin "2") (pinfunction "2_2") (pintype "passive"))
      (node (ref "TP4") (pin "TP") (pinfunction "TP_TP") (pintype "input"))
      (node (ref "U2") (pin "30") (pinfunction "PD0(RXD)_30") (pintype "bidirectional"))
    )
    (net (code "10") (name "AVR-TXD") (class "Default")
      (node (ref "R4") (pin "2") (pinfunction "2_2") (pintype "passive"))
      (node (ref "TP5") (pin "TP") (pinfunction "TP_TP") (pintype "input"))
      (node (ref "U2") (pin "31") (pinfunction "PD1(TXD)_31") (pintype "bidirectional"))
    )
    (net (code "11") (name "FILTER_OUTPUT") (class "Default")
      (node (ref "C14") (pin "2") (pinfunction "2_2") (pintype "passive"))
      (node (ref "FILTER_OUT") (pin "TP") (pinfunction "TP_TP") (pintype "input"))
      (node (ref "R23") (pin "1") (pinfunction "1_1") (pintype "passive"))
      (node (ref "R48") (pin "1") (pinfunction "1_1") (pintype "passive"))
      (node (ref "S2") (pin "P$5") (pinfunction "P_P$5") (pintype "passive"))
    )
    (net (code "12") (name "FREQ_CV") (class "Default")
      (node (ref "IC1") (pin "12") (pinfunction "12_12") (pintype "passive"))
      (node (ref "R21") (pin "1") (pinfunction "1_1") (pintype "passive"))
      (node (ref "R57") (pin "S") (pinfunction "S_S") (pintype "passive"))
      (node (ref "U4") (pin "2") (pinfunction "VOUTA_2") (pintype "output"))
    )
    (net (code "13") (name "FTDI-RXD") (class "Default")
      (node (ref "J2") (pin "5") (pinfunction "5_5") (pintype "passive"))
      (node (ref "R4") (pin "1") (pinfunction "1_1") (pintype "passive"))
    )
    (net (code "14") (name "FTDI-TXD") (class "Default")
      (node (ref "J2") (pin "4") (pinfunction "4_4") (pintype "passive"))
      (node (ref "R2") (pin "1") (pinfunction "1_1") (pintype "passive"))
    )
    (net (code "15") (name "GND") (class "Default")
      (node (ref "C1") (pin "2") (pinfunction "2_2") (pintype "passive"))
      (node (ref "C10") (pin "1") (pinfunction "1_1") (pintype "passive"))
      (node (ref "C12") (pin "2") (pinfunction "2_2") (pintype "passive"))
      (node (ref "C13") (pin "2") (pinfunction "2_2") (pintype "passive"))
      (node (ref "C15") (pin "2") (pinfunction "2_2") (pintype "passive"))
      (node (ref "C16") (pin "2") (pinfunction "2_2") (pintype "passive"))
      (node (ref "C19") (pin "2") (pinfunction "2_2") (pintype "passive"))
      (node (ref "C2") (pin "1") (pinfunction "1_1") (pintype "passive"))
      (node (ref "C20") (pin "2") (pinfunction "2_2") (pintype "passive"))
      (node (ref "C22") (pin "2") (pinfunction "2_2") (pintype "passive"))
      (node (ref "C23") (pin "2") (pinfunction "2_2") (pintype "passive"))
      (node (ref "C26") (pin "2") (pinfunction "2_2") (pintype "passive"))
      (node (ref "C3") (pin "2") (pinfunction "2_2") (pintype "passive"))
      (node (ref "C31") (pin "1") (pinfunction "1_1") (pintype "passive"))
      (node (ref "C35") (pin "2") (pinfunction "2_2") (pintype "passive"))
      (node (ref "C36") (pin "2") (pinfunction "2_2") (pintype "passive"))
      (node (ref "C37") (pin "2") (pinfunction "2_2") (pintype "passive"))
      (node (ref "C38") (pin "2") (pinfunction "2_2") (pintype "passive"))
      (node (ref "C39") (pin "2") (pinfunction "2_2") (pintype "passive"))
      (node (ref "C4") (pin "1") (pinfunction "1_1") (pintype "passive"))
      (node (ref "C40") (pin "1") (pinfunction "1_1") (pintype "passive"))
      (node (ref "C42") (pin "1") (pinfunction "1_1") (pintype "passive"))
      (node (ref "C43") (pin "1") (pinfunction "1_1") (pintype "passive"))
      (node (ref "C44") (pin "1") (pinfunction "1_1") (pintype "passive"))
      (node (ref "C45") (pin "1") (pinfunction "1_1") (pintype "passive"))
      (node (ref "C46") (pin "1") (pinfunction "1_1") (pintype "passive"))
      (node (ref "C47") (pin "1") (pinfunction "1_1") (pintype "passive"))
      (node (ref "C48") (pin "1") (pinfunction "1_1") (pintype "passive"))
      (node (ref "C49") (pin "1") (pinfunction "1_1") (pintype "passive"))
      (node (ref "C5") (pin "1") (pinfunction "1_1") (pintype "passive"))
      (node (ref "C50") (pin "2") (pinfunction "2_2") (pintype "passive"))
      (node (ref "C51") (pin "2") (pinfunction "2_2") (pintype "passive"))
      (node (ref "C6") (pin "1") (pinfunction "1_1") (pintype "passive"))
      (node (ref "C7") (pin "2") (pinfunction "2_2") (pintype "passive"))
      (node (ref "C8") (pin "2") (pinfunction "2_2") (pintype "passive"))
      (node (ref "C9") (pin "1") (pinfunction "1_1") (pintype "passive"))
      (node (ref "D2") (pin "C") (pinfunction "C_C") (pintype "passive"))
      (node (ref "IC1") (pin "3") (pinfunction "3_3") (pintype "passive"))
      (node (ref "IC2") (pin "4") (pinfunction "V-_4") (pintype "power_in"))
      (node (ref "IC3") (pin "3") (pinfunction "+IN_3") (pintype "input"))
      (node (ref "IC3") (pin "5") (pinfunction "+IN_5") (pintype "input"))
      (node (ref "IC4") (pin "4") (pinfunction "V-_4") (pintype "power_in"))
      (node (ref "J1") (pin "6") (pinfunction "6_6") (pintype "passive"))
      (node (ref "J2") (pin "1") (pinfunction "1_1") (pintype "passive"))
      (node (ref "J3") (pin "SLEEVE-NORM") (pinfunction "EARTH-NORM_SLEEVE-NORM") (pintype "bidirectional"))
      (node (ref "J4") (pin "GND") (pinfunction "GND_GND") (pintype "bidirectional"))
      (node (ref "J4") (pin "GNDBREAK") (pinfunction "GNDBREAK_GNDBREAK") (pintype "bidirectional"))
      (node (ref "J5") (pin "SLEEVE-NORM") (pinfunction "EARTH-NORM_SLEEVE-NORM") (pintype "bidirectional"))
      (node (ref "JP1") (pin "2") (pinfunction "2_2") (pintype "passive"))
      (node (ref "JP2") (pin "1") (pinfunction "1_1") (pintype "passive"))
      (node (ref "Q1") (pin "2") (pinfunction "S_2") (pintype "passive"))
      (node (ref "Q2") (pin "G") (pinfunction "G_G") (pintype "passive"))
      (node (ref "Q3") (pin "G") (pinfunction "G_G") (pintype "passive"))
      (node (ref "R21") (pin "2") (pinfunction "2_2") (pintype "passive"))
      (node (ref "R27") (pin "2") (pinfunction "2_2") (pintype "passive"))
      (node (ref "R30") (pin "1") (pinfunction "1_1") (pintype "passive"))
      (node (ref "R31") (pin "2") (pinfunction "2_2") (pintype "passive"))
      (node (ref "R32") (pin "2") (pinfunction "2_2") (pintype "passive"))
      (node (ref "R34") (pin "A") (pinfunction "A_A") (pintype "passive"))
      (node (ref "R34") (pin "S") (pinfunction "S_S") (pintype "passive"))
      (node (ref "R40") (pin "2") (pinfunction "2_2") (pintype "passive"))
      (node (ref "R42") (pin "1") (pinfunction "1_1") (pintype "passive"))
      (node (ref "R43") (pin "A") (pinfunction "A_A") (pintype "passive"))
      (node (ref "R44") (pin "A") (pinfunction "A_A") (pintype "passive"))
      (node (ref "R50") (pin "2") (pinfunction "2_2") (pintype "passive"))
      (node (ref "R51") (pin "2") (pinfunction "2_2") (pintype "passive"))
      (node (ref "R53") (pin "1") (pinfunction "1_1") (pintype "passive"))
      (node (ref "R55") (pin "1") (pinfunction "1_1") (pintype "passive"))
      (node (ref "R57") (pin "A") (pinfunction "A_A") (pintype "passive"))
      (node (ref "R59") (pin "A") (pinfunction "A_A") (pintype "passive"))
      (node (ref "R6") (pin "1") (pinfunction "1_1") (pintype "passive"))
      (node (ref "R60") (pin "2") (pinfunction "2_2") (pintype "passive"))
      (node (ref "SW1") (pin "1") (pinfunction "1_1") (pintype "passive"))
      (node (ref "U1") (pin "1") (pinfunction "GND/ADJ_1") (pintype "input"))
      (node (ref "U2") (pin "21") (pinfunction "GND_21") (pintype "bidirectional"))
      (node (ref "U2") (pin "3") (pinfunction "GND_3") (pintype "bidirectional"))
      (node (ref "U2") (pin "5") (pinfunction "GND_5") (pintype "bidirectional"))
      (node (ref "U3") (pin "16") (pinfunction "COMMON_16") (pintype "input"))
      (node (ref "U3") (pin "2") (pinfunction "-VIN_2") (pintype "input"))
      (node (ref "U3") (pin "3") (pinfunction "-VIN_3") (pintype "input"))
      (node (ref "U3") (pin "9") (pinfunction "COMMON_9") (pintype "input"))
      (node (ref "U4") (pin "10") (pinfunction "IND_10") (pintype "input"))
      (node (ref "U4") (pin "11") (pinfunction "INC_11") (pintype "input"))
      (node (ref "U4") (pin "13") (pinfunction "REFSEL_13") (pintype "input"))
      (node (ref "U4") (pin "16") (pinfunction "GND_16") (pintype "power_in"))
      (node (ref "U4") (pin "8") (pinfunction "GND_2_8") (pintype "power_in"))
      (node (ref "U5") (pin "3") (pinfunction "GND_3") (pintype "passive"))
      (node (ref "U5") (pin "6") (pinfunction "OSCB_6") (pintype "input"))
      (node (ref "U5") (pin "7") (pinfunction "OSCE_7") (pintype "output"))
      (node (ref "U6") (pin "4") (pinfunction "GND_4") (pintype "input"))
    )
    (net (code "16") (name "MISO") (class "Default")
      (node (ref "J1") (pin "1") (pinfunction "1_1") (pintype "passive"))
      (node (ref "U2") (pin "16") (pinfunction "PB4(MISO)_16") (pintype "bidirectional"))
    )
    (net (code "17") (name "MOSI") (class "Default")
      (node (ref "J1") (pin "4") (pinfunction "4_4") (pintype "passive"))
      (node (ref "U2") (pin "15") (pinfunction "PB3(MOSI/OC2)_15") (pintype "bidirectional"))
    )
    (net (code "18") (name "Net-(ANTENNA-P)") (class "Default")
      (node (ref "ANTENNA") (pin "1") (pinfunction "P_1") (pintype "passive"))
      (node (ref "C21") (pin "2") (pinfunction "2_2") (pintype "passive"))
    )
    (net (code "19") (name "Net-(C9-Pad2)") (class "Default")
      (node (ref "C9") (pin "2") (pinfunction "2_2") (pintype "passive"))
      (node (ref "IC1") (pin "5") (pinfunction "5_5") (pintype "passive"))
    )
    (net (code "20") (name "Net-(C10-Pad2)") (class "Default")
      (node (ref "C10") (pin "2") (pinfunction "2_2") (pintype "passive"))
      (node (ref "IC1") (pin "4") (pinfunction "4_4") (pintype "passive"))
    )
    (net (code "21") (name "Net-(C11-Pad2)") (class "Default")
      (node (ref "C11") (pin "2") (pinfunction "2_2") (pintype "passive"))
      (node (ref "R26") (pin "2") (pinfunction "2_2") (pintype "passive"))
    )
    (net (code "22") (name "Net-(C12-Pad1)") (class "Default")
      (node (ref "C12") (pin "1") (pinfunction "1_1") (pintype "passive"))
      (node (ref "IC1") (pin "16") (pinfunction "16_16") (pintype "passive"))
    )
    (net (code "23") (name "Net-(C13-Pad1)") (class "Default")
      (node (ref "C13") (pin "1") (pinfunction "1_1") (pintype "passive"))
      (node (ref "IC1") (pin "11") (pinfunction "11_11") (pintype "passive"))
    )
    (net (code "24") (name "Net-(C14-Pad1)") (class "Default")
      (node (ref "C14") (pin "1") (pinfunction "1_1") (pintype "passive"))
      (node (ref "IC1") (pin "10") (pinfunction "10_10") (pintype "passive"))
      (node (ref "R15") (pin "2") (pinfunction "2_2") (pintype "passive"))
    )
    (net (code "25") (name "Net-(C15-Pad1)") (class "Default")
      (node (ref "C15") (pin "1") (pinfunction "1_1") (pintype "passive"))
      (node (ref "L1") (pin "1") (pinfunction "1_1") (pintype "passive"))
      (node (ref "R24") (pin "1") (pinfunction "1_1") (pintype "passive"))
    )
    (net (code "26") (name "Net-(C16-Pad1)") (class "Default")
      (node (ref "C16") (pin "1") (pinfunction "1_1") (pintype "passive"))
      (node (ref "C17") (pin "2") (pinfunction "2_2") (pintype "passive"))
      (node (ref "Q2") (pin "S") (pinfunction "S_S") (pintype "passive"))
      (node (ref "R34") (pin "E") (pinfunction "E_E") (pintype "passive"))
    )
    (net (code "27") (name "Net-(C18-Pad1)") (class "Default")
      (node (ref "C18") (pin "1") (pinfunction "1_1") (pintype "passive"))
      (node (ref "R28") (pin "1") (pinfunction "1_1") (pintype "passive"))
    )
    (net (code "28") (name "Net-(C18-Pad2)") (class "Default")
      (node (ref "C18") (pin "2") (pinfunction "2_2") (pintype "passive"))
      (node (ref "JP8") (pin "2") (pinfunction "2_2") (pintype "passive"))
    )
    (net (code "29") (name "Net-(C21-Pad1)") (class "Default")
      (node (ref "C21") (pin "1") (pinfunction "1_1") (pintype "passive"))
      (node (ref "L2") (pin "2") (pinfunction "2_2") (pintype "passive"))
    )
    (net (code "30") (name "Net-(C23-Pad1)") (class "Default")
      (node (ref "C23") (pin "1") (pinfunction "1_1") (pintype "passive"))
      (node (ref "C24") (pin "2") (pinfunction "2_2") (pintype "passive"))
      (node (ref "Q3") (pin "S") (pinfunction "S_S") (pintype "passive"))
      (node (ref "R27") (pin "1") (pinfunction "1_1") (pintype "passive"))
    )
    (net (code "31") (name "Net-(C24-Pad1)") (class "Default")
      (node (ref "C24") (pin "1") (pinfunction "1_1") (pintype "passive"))
      (node (ref "JP3") (pin "1") (pinfunction "1_1") (pintype "passive"))
      (node (ref "L2") (pin "1") (pinfunction "1_1") (pintype "passive"))
      (node (ref "L3") (pin "2") (pinfunction "2_2") (pintype "passive"))
      (node (ref "Q3") (pin "D") (pinfunction "D_D") (pintype "passive"))
    )
    (net (code "32") (name "Net-(C25-Pad1)") (class "Default")
      (node (ref "C25") (pin "1") (pinfunction "1_1") (pintype "passive"))
      (node (ref "R33") (pin "2") (pinfunction "2_2") (pintype "passive"))
    )
    (net (code "33") (name "Net-(C25-Pad2)") (class "Default")
      (node (ref "C25") (pin "2") (pinfunction "2_2") (pintype "passive"))
      (node (ref "JP4") (pin "1") (pinfunction "1_1") (pintype "passive"))
    )
    (net (code "34") (name "Net-(C26-Pad1)") (class "Default")
      (node (ref "C26") (pin "1") (pinfunction "1_1") (pintype "passive"))
      (node (ref "L3") (pin "1") (pinfunction "1_1") (pintype "passive"))
      (node (ref "R29") (pin "2") (pinfunction "2_2") (pintype "passive"))
    )
    (net (code "35") (name "Net-(C27-Pad1)") (class "Default")
      (node (ref "C27") (pin "1") (pinfunction "1_1") (pintype "passive"))
      (node (ref "JP3") (pin "2") (pinfunction "2_2") (pintype "passive"))
    )
    (net (code "36") (name "Net-(C28-Pad1)") (class "Default")
      (node (ref "C28") (pin "1") (pinfunction "1_1") (pintype "passive"))
      (node (ref "JP6") (pin "2") (pinfunction "2_2") (pintype "passive"))
    )
    (net (code "37") (name "Net-(C28-Pad2)") (class "Default")
      (node (ref "C28") (pin "2") (pinfunction "2_2") (pintype "passive"))
      (node (ref "R38") (pin "2") (pinfunction "2_2") (pintype "passive"))
    )
    (net (code "38") (name "Net-(C29-Pad1)") (class "Default")
      (node (ref "C29") (pin "1") (pinfunction "1_1") (pintype "passive"))
      (node (ref "JP5") (pin "2") (pinfunction "2_2") (pintype "passive"))
    )
    (net (code "39") (name "Net-(C29-Pad2)") (class "Default")
      (node (ref "C29") (pin "2") (pinfunction "2_2") (pintype "passive"))
      (node (ref "R39") (pin "2") (pinfunction "2_2") (pintype "passive"))
    )
    (net (code "40") (name "Net-(C30-Pad1)") (class "Default")
      (node (ref "C30") (pin "1") (pinfunction "1_1") (pintype "passive"))
      (node (ref "JP7") (pin "1") (pinfunction "1_1") (pintype "passive"))
      (node (ref "L4") (pin "2") (pinfunction "2_2") (pintype "passive"))
      (node (ref "Q4") (pin "D") (pinfunction "D_D") (pintype "passive"))
    )
    (net (code "41") (name "Net-(C31-Pad2)") (class "Default")
      (node (ref "C31") (pin "2") (pinfunction "2_2") (pintype "passive"))
      (node (ref "Q4") (pin "S") (pinfunction "S_S") (pintype "passive"))
      (node (ref "R40") (pin "1") (pinfunction "1_1") (pintype "passive"))
    )
    (net (code "42") (name "Net-(C32-Pad1)") (class "Default")
      (node (ref "C32") (pin "1") (pinfunction "1_1") (pintype "passive"))
      (node (ref "R35") (pin "2") (pinfunction "2_2") (pintype "passive"))
    )
    (net (code "43") (name "Net-(C32-Pad2)") (class "Default")
      (node (ref "C32") (pin "2") (pinfunction "2_2") (pintype "passive"))
      (node (ref "JP7") (pin "2") (pinfunction "2_2") (pintype "passive"))
    )
    (net (code "44") (name "Net-(C41-Pad1)") (class "Default")
      (node (ref "C41") (pin "1") (pinfunction "1_1") (pintype "passive"))
      (node (ref "JP9") (pin "1") (pinfunction "1_1") (pintype "passive"))
    )
    (net (code "45") (name "Net-(D1-PadA)") (class "Default")
      (node (ref "D1") (pin "A") (pinfunction "A_A") (pintype "passive"))
      (node (ref "D4") (pin "A") (pinfunction "A_A") (pintype "passive"))
      (node (ref "D5") (pin "A") (pinfunction "A_A") (pintype "passive"))
      (node (ref "J4") (pin "PWR") (pinfunction "PWR_PWR") (pintype "bidirectional"))
    )
    (net (code "46") (name "Net-(D2-PadA)") (class "Default")
      (node (ref "D2") (pin "A") (pinfunction "A_A") (pintype "passive"))
      (node (ref "R3") (pin "1") (pinfunction "1_1") (pintype "passive"))
    )
    (net (code "47") (name "Net-(D3-PadA)") (class "Default")
      (node (ref "D3") (pin "A") (pinfunction "A_A") (pintype "passive"))
      (node (ref "R5") (pin "1") (pinfunction "1_1") (pintype "passive"))
    )
    (net (code "48") (name "Net-(D4-PadC)") (class "Default")
      (node (ref "D4") (pin "C") (pinfunction "C_C") (pintype "passive"))
      (node (ref "U3") (pin "22") (pinfunction "+VIN_22") (pintype "power_in"))
      (node (ref "U3") (pin "23") (pinfunction "+VIN_23") (pintype "power_in"))
    )
    (net (code "49") (name "Net-(IC1-Pad1)") (class "Default")
      (node (ref "IC1") (pin "1") (pinfunction "1_1") (pintype "passive"))
      (node (ref "R7") (pin "2") (pinfunction "2_2") (pintype "passive"))
      (node (ref "R9") (pin "2") (pinfunction "2_2") (pintype "passive"))
    )
    (net (code "50") (name "Net-(IC1-Pad2)") (class "Default")
      (node (ref "IC1") (pin "2") (pinfunction "2_2") (pintype "passive"))
      (node (ref "R10") (pin "2") (pinfunction "2_2") (pintype "passive"))
      (node (ref "R11") (pin "2") (pinfunction "2_2") (pintype "passive"))
      (node (ref "R12") (pin "1") (pinfunction "1_1") (pintype "passive"))
    )
    (net (code "51") (name "Net-(IC1-Pad6)") (class "Default")
      (node (ref "IC1") (pin "6") (pinfunction "6_6") (pintype "passive"))
      (node (ref "R11") (pin "1") (pinfunction "1_1") (pintype "passive"))
      (node (ref "R17") (pin "2") (pinfunction "2_2") (pintype "passive"))
    )
    (net (code "52") (name "Net-(IC1-Pad7)") (class "Default")
      (node (ref "IC1") (pin "7") (pinfunction "7_7") (pintype "passive"))
      (node (ref "R10") (pin "1") (pinfunction "1_1") (pintype "passive"))
      (node (ref "R9") (pin "1") (pinfunction "1_1") (pintype "passive"))
    )
    (net (code "53") (name "Net-(IC1-Pad8)") (class "Default")
      (node (ref "IC1") (pin "8") (pinfunction "8_8") (pintype "passive"))
      (node (ref "R23") (pin "2") (pinfunction "2_2") (pintype "passive"))
    )
    (net (code "54") (name "Net-(IC1-Pad9)") (class "Default")
      (node (ref "IC1") (pin "9") (pinfunction "9_9") (pintype "passive"))
      (node (ref "R22") (pin "2") (pinfunction "2_2") (pintype "passive"))
    )
    (net (code "55") (name "Net-(IC1-Pad13)") (class "Default")
      (node (ref "IC1") (pin "13") (pinfunction "13_13") (pintype "passive"))
      (node (ref "R19") (pin "1") (pinfunction "1_1") (pintype "passive"))
    )
    (net (code "56") (name "Net-(IC1-Pad15)") (class "Default")
      (node (ref "IC1") (pin "15") (pinfunction "15_15") (pintype "passive"))
      (node (ref "R16") (pin "2") (pinfunction "2_2") (pintype "passive"))
      (node (ref "R18") (pin "2") (pinfunction "2_2") (pintype "passive"))
    )
    (net (code "57") (name "Net-(IC1-Pad17)") (class "Default")
      (node (ref "IC1") (pin "17") (pinfunction "17_17") (pintype "passive"))
      (node (ref "R14") (pin "2") (pinfunction "2_2") (pintype "passive"))
      (node (ref "R17") (pin "1") (pinfunction "1_1") (pintype "passive"))
      (node (ref "R18") (pin "1") (pinfunction "1_1") (pintype "passive"))
    )
    (net (code "58") (name "Net-(IC1-Pad18)") (class "Default")
      (node (ref "IC1") (pin "18") (pinfunction "18_18") (pintype "passive"))
      (node (ref "R13") (pin "2") (pinfunction "2_2") (pintype "passive"))
      (node (ref "R15") (pin "1") (pinfunction "1_1") (pintype "passive"))
      (node (ref "R16") (pin "1") (pinfunction "1_1") (pintype "passive"))
    )
    (net (code "59") (name "Net-(IC2A-+IN)") (class "Default")
      (node (ref "IC2") (pin "3") (pinfunction "+IN_3") (pintype "input"))
      (node (ref "R25") (pin "1") (pinfunction "1_1") (pintype "passive"))
      (node (ref "R30") (pin "2") (pinfunction "2_2") (pintype "passive"))
    )
    (net (code "60") (name "Net-(IC2A--IN)") (class "Default")
      (node (ref "IC2") (pin "2") (pinfunction "-IN_2") (pintype "input"))
      (node (ref "R26") (pin "1") (pinfunction "1_1") (pintype "passive"))
      (node (ref "R36") (pin "E") (pinfunction "E_E") (pintype "passive"))
    )
    (net (code "61") (name "Net-(IC2A-OUT)") (class "Default")
      (node (ref "IC2") (pin "1") (pinfunction "OUT_1") (pintype "output"))
      (node (ref "JP5") (pin "1") (pinfunction "1_1") (pintype "passive"))
      (node (ref "R36") (pin "A") (pinfunction "A_A") (pintype "passive"))
      (node (ref "R36") (pin "S") (pinfunction "S_S") (pintype "passive"))
    )
    (net (code "62") (name "Net-(IC2B-+IN)") (class "Default")
      (node (ref "IC2") (pin "5") (pinfunction "+IN_5") (pintype "input"))
      (node (ref "R52") (pin "1") (pinfunction "1_1") (pintype "passive"))
      (node (ref "R53") (pin "2") (pinfunction "2_2") (pintype "passive"))
    )
    (net (code "63") (name "Net-(IC2B--IN)") (class "Default")
      (node (ref "IC2") (pin "6") (pinfunction "-IN_6") (pintype "input"))
      (node (ref "IC2") (pin "7") (pinfunction "OUT_7") (pintype "output"))
    )
    (net (code "64") (name "Net-(IC3A--IN)") (class "Default")
      (node (ref "IC3") (pin "2") (pinfunction "-IN_2") (pintype "input"))
      (node (ref "R45") (pin "E") (pinfunction "E_E") (pintype "passive"))
      (node (ref "R46") (pin "2") (pinfunction "2_2") (pintype "passive"))
    )
    (net (code "65") (name "Net-(IC3A-OUT)") (class "Default")
      (node (ref "IC3") (pin "1") (pinfunction "OUT_1") (pintype "output"))
      (node (ref "R45") (pin "A") (pinfunction "A_A") (pintype "passive"))
      (node (ref "R45") (pin "S") (pinfunction "S_S") (pintype "passive"))
      (node (ref "R7") (pin "1") (pinfunction "1_1") (pintype "passive"))
    )
    (net (code "66") (name "Net-(IC3B--IN)") (class "Default")
      (node (ref "IC3") (pin "6") (pinfunction "-IN_6") (pintype "input"))
      (node (ref "R47") (pin "E") (pinfunction "E_E") (pintype "passive"))
      (node (ref "R48") (pin "2") (pinfunction "2_2") (pintype "passive"))
    )
    (net (code "67") (name "Net-(IC4A-+IN)") (class "Default")
      (node (ref "IC4") (pin "3") (pinfunction "+IN_3") (pintype "input"))
      (node (ref "R41") (pin "2") (pinfunction "2_2") (pintype "passive"))
      (node (ref "R42") (pin "2") (pinfunction "2_2") (pintype "passive"))
    )
    (net (code "68") (name "Net-(IC4A--IN)") (class "Default")
      (node (ref "IC4") (pin "2") (pinfunction "-IN_2") (pintype "input"))
      (node (ref "R35") (pin "1") (pinfunction "1_1") (pintype "passive"))
      (node (ref "R37") (pin "E") (pinfunction "E_E") (pintype "passive"))
    )
    (net (code "69") (name "Net-(IC4A-OUT)") (class "Default")
      (node (ref "IC4") (pin "1") (pinfunction "OUT_1") (pintype "output"))
      (node (ref "R28") (pin "2") (pinfunction "2_2") (pintype "passive"))
      (node (ref "R37") (pin "A") (pinfunction "A_A") (pintype "passive"))
      (node (ref "R37") (pin "S") (pinfunction "S_S") (pintype "passive"))
    )
    (net (code "70") (name "Net-(IC4B-+IN)") (class "Default")
      (node (ref "IC4") (pin "5") (pinfunction "+IN_5") (pintype "input"))
      (node (ref "R54") (pin "1") (pinfunction "1_1") (pintype "passive"))
      (node (ref "R55") (pin "2") (pinfunction "2_2") (pintype "passive"))
    )
    (net (code "71") (name "Net-(IC4B--IN)") (class "Default")
      (node (ref "IC4") (pin "6") (pinfunction "-IN_6") (pintype "input"))
      (node (ref "IC4") (pin "7") (pinfunction "OUT_7") (pintype "output"))
    )
    (net (code "72") (name "Net-(J2-Pad3)") (class "Default")
      (node (ref "J2") (pin "3") (pinfunction "3_3") (pintype "passive"))
      (node (ref "TP6") (pin "TP") (pinfunction "TP_TP") (pintype "input"))
    )
    (net (code "73") (name "Net-(LD1-AG)") (class "Default")
      (node (ref "LD1") (pin "AX") (pinfunction "AG_AX") (pintype "passive"))
      (node (ref "S2") (pin "P$9") (pinfunction "S_P$9") (pintype "passive"))
    )
    (net (code "74") (name "Net-(LD1-PadC)") (class "Default")
      (node (ref "LD1") (pin "C") (pinfunction "C_C") (pintype "passive"))
      (node (ref "R60") (pin "1") (pinfunction "1_1") (pintype "passive"))
    )
    (net (code "75") (name "Net-(PAD1-P)") (class "Default")
      (node (ref "C17") (pin "1") (pinfunction "1_1") (pintype "passive"))
      (node (ref "JP6") (pin "1") (pinfunction "1_1") (pintype "passive"))
      (node (ref "L1") (pin "2") (pinfunction "2_2") (pintype "passive"))
      (node (ref "PAD1") (pin "1") (pinfunction "P_1") (pintype "passive"))
      (node (ref "Q2") (pin "D") (pinfunction "D_D") (pintype "passive"))
    )
    (net (code "76") (name "Net-(PAD2-P)") (class "Default")
      (node (ref "JP1") (pin "1") (pinfunction "1_1") (pintype "passive"))
      (node (ref "PAD2") (pin "1") (pinfunction "P_1") (pintype "passive"))
    )
    (net (code "77") (name "Net-(PAD3-P)") (class "Default")
      (node (ref "JP2") (pin "2") (pinfunction "2_2") (pintype "passive"))
      (node (ref "PAD3") (pin "1") (pinfunction "P_1") (pintype "passive"))
    )
    (net (code "78") (name "Net-(Q1-D)") (class "Default")
      (node (ref "D3") (pin "C") (pinfunction "C_C") (pintype "passive"))
      (node (ref "Q1") (pin "1") (pinfunction "D_1") (pintype "passive"))
    )
    (net (code "79") (name "Net-(Q4-PadG)") (class "Default")
      (node (ref "Q4") (pin "G") (pinfunction "G_G") (pintype "passive"))
      (node (ref "R38") (pin "1") (pinfunction "1_1") (pintype "passive"))
      (node (ref "R39") (pin "1") (pinfunction "1_1") (pintype "passive"))
    )
    (net (code "80") (name "Net-(Q6-B)") (class "Default")
      (node (ref "C27") (pin "2") (pinfunction "2_2") (pintype "passive"))
      (node (ref "Q6") (pin "2") (pinfunction "B_2") (pintype "passive"))
    )
    (net (code "81") (name "Net-(Q6-E)") (class "Default")
      (node (ref "Q6") (pin "3") (pinfunction "E_3") (pintype "passive"))
      (node (ref "Q7") (pin "2") (pinfunction "B_2") (pintype "passive"))
      (node (ref "R31") (pin "1") (pinfunction "1_1") (pintype "passive"))
    )
    (net (code "82") (name "Net-(Q7-E)") (class "Default")
      (node (ref "Q7") (pin "3") (pinfunction "E_3") (pintype "passive"))
      (node (ref "R32") (pin "1") (pinfunction "1_1") (pintype "passive"))
      (node (ref "R33") (pin "1") (pinfunction "1_1") (pintype "passive"))
    )
    (net (code "83") (name "Net-(R20-Pad1)") (class "Default")
      (node (ref "R20") (pin "1") (pinfunction "1_1") (pintype "passive"))
      (node (ref "R44") (pin "E") (pinfunction "E_E") (pintype "passive"))
    )
    (net (code "84") (name "Net-(R43-PadE)") (class "Default")
      (node (ref "R43") (pin "E") (pinfunction "E_E") (pintype "passive"))
      (node (ref "R8") (pin "1") (pinfunction "1_1") (pintype "passive"))
    )
    (net (code "85") (name "Net-(R56-Pad1)") (class "Default")
      (node (ref "R56") (pin "1") (pinfunction "1_1") (pintype "passive"))
      (node (ref "R57") (pin "E") (pinfunction "E_E") (pintype "passive"))
    )
    (net (code "86") (name "Net-(R58-Pad1)") (class "Default")
      (node (ref "R58") (pin "1") (pinfunction "1_1") (pintype "passive"))
      (node (ref "R59") (pin "E") (pinfunction "E_E") (pintype "passive"))
    )
    (net (code "87") (name "Net-(S2A-P)") (class "Default")
      (node (ref "J5") (pin "RING-NORM") (pinfunction "RING-NORM_RING-NORM") (pintype "bidirectional"))
      (node (ref "J5") (pin "TIP-NORM") (pinfunction "TIP-NORM_TIP-NORM") (pintype "bidirectional"))
      (node (ref "S2") (pin "P$2") (pinfunction "P_P$2") (pintype "passive"))
    )
    (net (code "88") (name "Net-(S2B-O)") (class "Default")
      (node (ref "R50") (pin "1") (pinfunction "1_1") (pintype "passive"))
      (node (ref "S2") (pin "P$4") (pinfunction "O_P$4") (pintype "passive"))
    )
    (net (code "89") (name "Net-(S2C-O)") (class "Default")
      (node (ref "LD1") (pin "AR") (pinfunction "AR_AR") (pintype "passive"))
      (node (ref "S2") (pin "P$7") (pinfunction "O_P$7") (pintype "passive"))
    )
    (net (code "90") (name "Net-(U3-+VOUT)") (class "Default")
      (node (ref "JP10") (pin "1") (pinfunction "1_1") (pintype "passive"))
      (node (ref "U3") (pin "14") (pinfunction "+VOUT_14") (pintype "output"))
    )
    (net (code "91") (name "Net-(U3--VOUT)") (class "Default")
      (node (ref "JP11") (pin "2") (pinfunction "2_2") (pintype "passive"))
      (node (ref "U3") (pin "11") (pinfunction "-VOUT_11") (pintype "output"))
    )
    (net (code "92") (name "Net-(U5-INA)") (class "Default")
      (node (ref "JP4") (pin "2") (pinfunction "2_2") (pintype "passive"))
      (node (ref "U5") (pin "1") (pinfunction "INA_1") (pintype "input"))
    )
    (net (code "93") (name "Net-(U5-INB)") (class "Default")
      (node (ref "JP8") (pin "1") (pinfunction "1_1") (pintype "passive"))
      (node (ref "U5") (pin "2") (pinfunction "INB_2") (pintype "input"))
    )
    (net (code "94") (name "Net-(U5-OUTA)") (class "Default")
      (node (ref "C40") (pin "2") (pinfunction "2_2") (pintype "passive"))
      (node (ref "C41") (pin "2") (pinfunction "2_2") (pintype "passive"))
      (node (ref "U5") (pin "4") (pinfunction "OUTA_4") (pintype "output"))
    )
    (net (code "95") (name "Net-(U5-OUTB)") (class "Default")
      (node (ref "R51") (pin "1") (pinfunction "1_1") (pintype "passive"))
      (node (ref "U5") (pin "5") (pinfunction "OUTB_5") (pintype "output"))
    )
    (net (code "96") (name "Net-(U6-IN)") (class "Default")
      (node (ref "C50") (pin "1") (pinfunction "1_1") (pintype "passive"))
      (node (ref "D5") (pin "C") (pinfunction "C_C") (pintype "passive"))
      (node (ref "U6") (pin "1") (pinfunction "IN_1") (pintype "input"))
    )
    (net (code "97") (name "OUTPUT") (class "Default")
      (node (ref "IC3") (pin "7") (pinfunction "OUT_7") (pintype "output"))
      (node (ref "J3") (pin "RING-NORM") (pinfunction "RING-NORM_RING-NORM") (pintype "bidirectional"))
      (node (ref "J3") (pin "TIP-NORM") (pinfunction "TIP-NORM_TIP-NORM") (pintype "bidirectional"))
      (node (ref "R47") (pin "A") (pinfunction "A_A") (pintype "passive"))
      (node (ref "R47") (pin "S") (pinfunction "S_S") (pintype "passive"))
      (node (ref "S2") (pin "P$1") (pinfunction "O_P$1") (pintype "passive"))
      (node (ref "S2") (pin "P$6") (pinfunction "S_P$6") (pintype "passive"))
    )
    (net (code "98") (name "PWM_A") (class "Default")
      (node (ref "U2") (pin "9") (pinfunction "PD5(T1)_9") (pintype "bidirectional"))
      (node (ref "U4") (pin "6") (pinfunction "INA_6") (pintype "input"))
    )
    (net (code "99") (name "PWM_B") (class "Default")
      (node (ref "U2") (pin "10") (pinfunction "PD6(AIN0)_10") (pintype "bidirectional"))
      (node (ref "U4") (pin "5") (pinfunction "INB_5") (pintype "input"))
    )
    (net (code "100") (name "RES_CV") (class "Default")
      (node (ref "R22") (pin "1") (pinfunction "1_1") (pintype "passive"))
      (node (ref "R59") (pin "S") (pinfunction "S_S") (pintype "passive"))
      (node (ref "U4") (pin "3") (pinfunction "VOUTB_3") (pintype "output"))
    )
    (net (code "101") (name "SCK") (class "Default")
      (node (ref "J1") (pin "3") (pinfunction "3_3") (pintype "passive"))
      (node (ref "Q1") (pin "3") (pinfunction "G_3") (pintype "passive"))
      (node (ref "R6") (pin "2") (pinfunction "2_2") (pintype "passive"))
      (node (ref "U2") (pin "17") (pinfunction "PB5(SCK)_17") (pintype "bidirectional"))
    )
    (net (code "102") (name "THEREMIN_OUT") (class "Default")
      (node (ref "JP9") (pin "2") (pinfunction "2_2") (pintype "passive"))
      (node (ref "R46") (pin "1") (pinfunction "1_1") (pintype "passive"))
    )
    (net (code "103") (name "VIN") (class "Default")
      (node (ref "C1") (pin "1") (pinfunction "1_1") (pintype "passive"))
      (node (ref "D1") (pin "C") (pinfunction "C_C") (pintype "passive"))
      (node (ref "TP1") (pin "TP") (pinfunction "TP_TP") (pintype "input"))
      (node (ref "U1") (pin "3") (pinfunction "IN_3") (pintype "input"))
    )
    (net (code "104") (name "XTAL1") (class "Default")
      (node (ref "C7") (pin "1") (pinfunction "1_1") (pintype "passive"))
      (node (ref "U2") (pin "8") (pinfunction "PB7(XTAL2/TOSC2)_8") (pintype "bidirectional"))
      (node (ref "X1") (pin "1") (pinfunction "1_1") (pintype "passive"))
    )
    (net (code "105") (name "XTAL2") (class "Default")
      (node (ref "C8") (pin "1") (pinfunction "1_1") (pintype "passive"))
      (node (ref "U2") (pin "7") (pinfunction "PB6(XTAL1/TOSC1)_7") (pintype "bidirectional"))
      (node (ref "X1") (pin "2") (pinfunction "2_2") (pintype "passive"))
    )
    (net (code "106") (name "unconnected-(J2-Pad2)") (class "Default")
      (node (ref "J2") (pin "2") (pinfunction "2_2") (pintype "passive"))
    )
    (net (code "107") (name "unconnected-(J2-Pad6)") (class "Default")
      (node (ref "J2") (pin "6") (pinfunction "6_6") (pintype "passive"))
    )
    (net (code "108") (name "unconnected-(J3-EARTH-PadSLEEVE)") (class "Default")
      (node (ref "J3") (pin "SLEEVE") (pinfunction "EARTH_SLEEVE") (pintype "bidirectional"))
    )
    (net (code "109") (name "unconnected-(J3-PadRING)") (class "Default")
      (node (ref "J3") (pin "RING") (pinfunction "RING_RING") (pintype "bidirectional"))
    )
    (net (code "110") (name "unconnected-(J3-PadTIP)") (class "Default")
      (node (ref "J3") (pin "TIP") (pinfunction "TIP_TIP") (pintype "bidirectional"))
    )
    (net (code "111") (name "unconnected-(J5-EARTH-PadSLEEVE)") (class "Default")
      (node (ref "J5") (pin "SLEEVE") (pinfunction "EARTH_SLEEVE") (pintype "bidirectional"))
    )
    (net (code "112") (name "unconnected-(J5-PadRING)") (class "Default")
      (node (ref "J5") (pin "RING") (pinfunction "RING_RING") (pintype "bidirectional"))
    )
    (net (code "113") (name "unconnected-(J5-PadTIP)") (class "Default")
      (node (ref "J5") (pin "TIP") (pinfunction "TIP_TIP") (pintype "bidirectional"))
    )
    (net (code "114") (name "unconnected-(U2-AREF-Pad20)") (class "Default")
      (node (ref "U2") (pin "20") (pinfunction "AREF_20") (pintype "bidirectional"))
    )
    (net (code "115") (name "unconnected-(U2-PB0(ICP)-Pad12)") (class "Default")
      (node (ref "U2") (pin "12") (pinfunction "PB0(ICP)_12") (pintype "bidirectional"))
    )
    (net (code "116") (name "unconnected-(U2-PB1(OC1A)-Pad13)") (class "Default")
      (node (ref "U2") (pin "13") (pinfunction "PB1(OC1A)_13") (pintype "bidirectional"))
    )
    (net (code "117") (name "unconnected-(U2-PB2(SS{slash}OC1B)-Pad14)") (class "Default")
      (node (ref "U2") (pin "14") (pinfunction "PB2(SS/OC1B)_14") (pintype "bidirectional"))
    )
    (net (code "118") (name "unconnected-(U2-PC0(ADC0)-Pad23)") (class "Default")
      (node (ref "U2") (pin "23") (pinfunction "PC0(ADC0)_23") (pintype "bidirectional"))
    )
    (net (code "119") (name "unconnected-(U2-PC1(ADC1)-Pad24)") (class "Default")
      (node (ref "U2") (pin "24") (pinfunction "PC1(ADC1)_24") (pintype "bidirectional"))
    )
    (net (code "120") (name "unconnected-(U2-PC2(ADC2)-Pad25)") (class "Default")
      (node (ref "U2") (pin "25") (pinfunction "PC2(ADC2)_25") (pintype "bidirectional"))
    )
    (net (code "121") (name "unconnected-(U2-PC3(ADC3)-Pad26)") (class "Default")
      (node (ref "U2") (pin "26") (pinfunction "PC3(ADC3)_26") (pintype "bidirectional"))
    )
    (net (code "122") (name "unconnected-(U2-PC4(ADC4{slash}SDA)-Pad27)") (class "Default")
      (node (ref "U2") (pin "27") (pinfunction "PC4(ADC4/SDA)_27") (pintype "bidirectional"))
    )
    (net (code "123") (name "unconnected-(U2-PC5(ADC5{slash}SCL)-Pad28)") (class "Default")
      (node (ref "U2") (pin "28") (pinfunction "PC5(ADC5/SCL)_28") (pintype "bidirectional"))
    )
    (net (code "124") (name "unconnected-(U2-PD2(INT0)-Pad32)") (class "Default")
      (node (ref "U2") (pin "32") (pinfunction "PD2(INT0)_32") (pintype "bidirectional"))
    )
    (net (code "125") (name "unconnected-(U2-PD3(INT1)-Pad1)") (class "Default")
      (node (ref "U2") (pin "1") (pinfunction "PD3(INT1)_1") (pintype "bidirectional"))
    )
    (net (code "126") (name "unconnected-(U2-PD4(XCK{slash}T0)-Pad2)") (class "Default")
      (node (ref "U2") (pin "2") (pinfunction "PD4(XCK/T0)_2") (pintype "bidirectional"))
    )
    (net (code "127") (name "unconnected-(U2-PD7(AIN1)-Pad11)") (class "Default")
      (node (ref "U2") (pin "11") (pinfunction "PD7(AIN1)_11") (pintype "bidirectional"))
    )
    (net (code "128") (name "unconnected-(U4-REF-Pad12)") (class "Default")
      (node (ref "U4") (pin "12") (pinfunction "REF_12") (pintype "bidirectional"))
    )
    (net (code "129") (name "unconnected-(U4-VOUTC-Pad14)") (class "Default")
      (node (ref "U4") (pin "14") (pinfunction "VOUTC_14") (pintype "output"))
    )
    (net (code "130") (name "unconnected-(U4-VOUTD-Pad15)") (class "Default")
      (node (ref "U4") (pin "15") (pinfunction "VOUTD_15") (pintype "output"))
    )
    (net (code "131") (name "~{RESET}") (class "Default")
      (node (ref "J1") (pin "5") (pinfunction "5_5") (pintype "passive"))
      (node (ref "R1") (pin "1") (pinfunction "1_1") (pintype "passive"))
      (node (ref "SW1") (pin "3") (pinfunction "2_3") (pintype "passive"))
      (node (ref "TP3") (pin "TP") (pinfunction "TP_TP") (pintype "input"))
      (node (ref "U2") (pin "29") (pinfunction "PC6(/RESET)_29") (pintype "bidirectional"))
    )
  )
)
